# CPU.net
KiCad netlist of a schematic drawn in Altium Designer
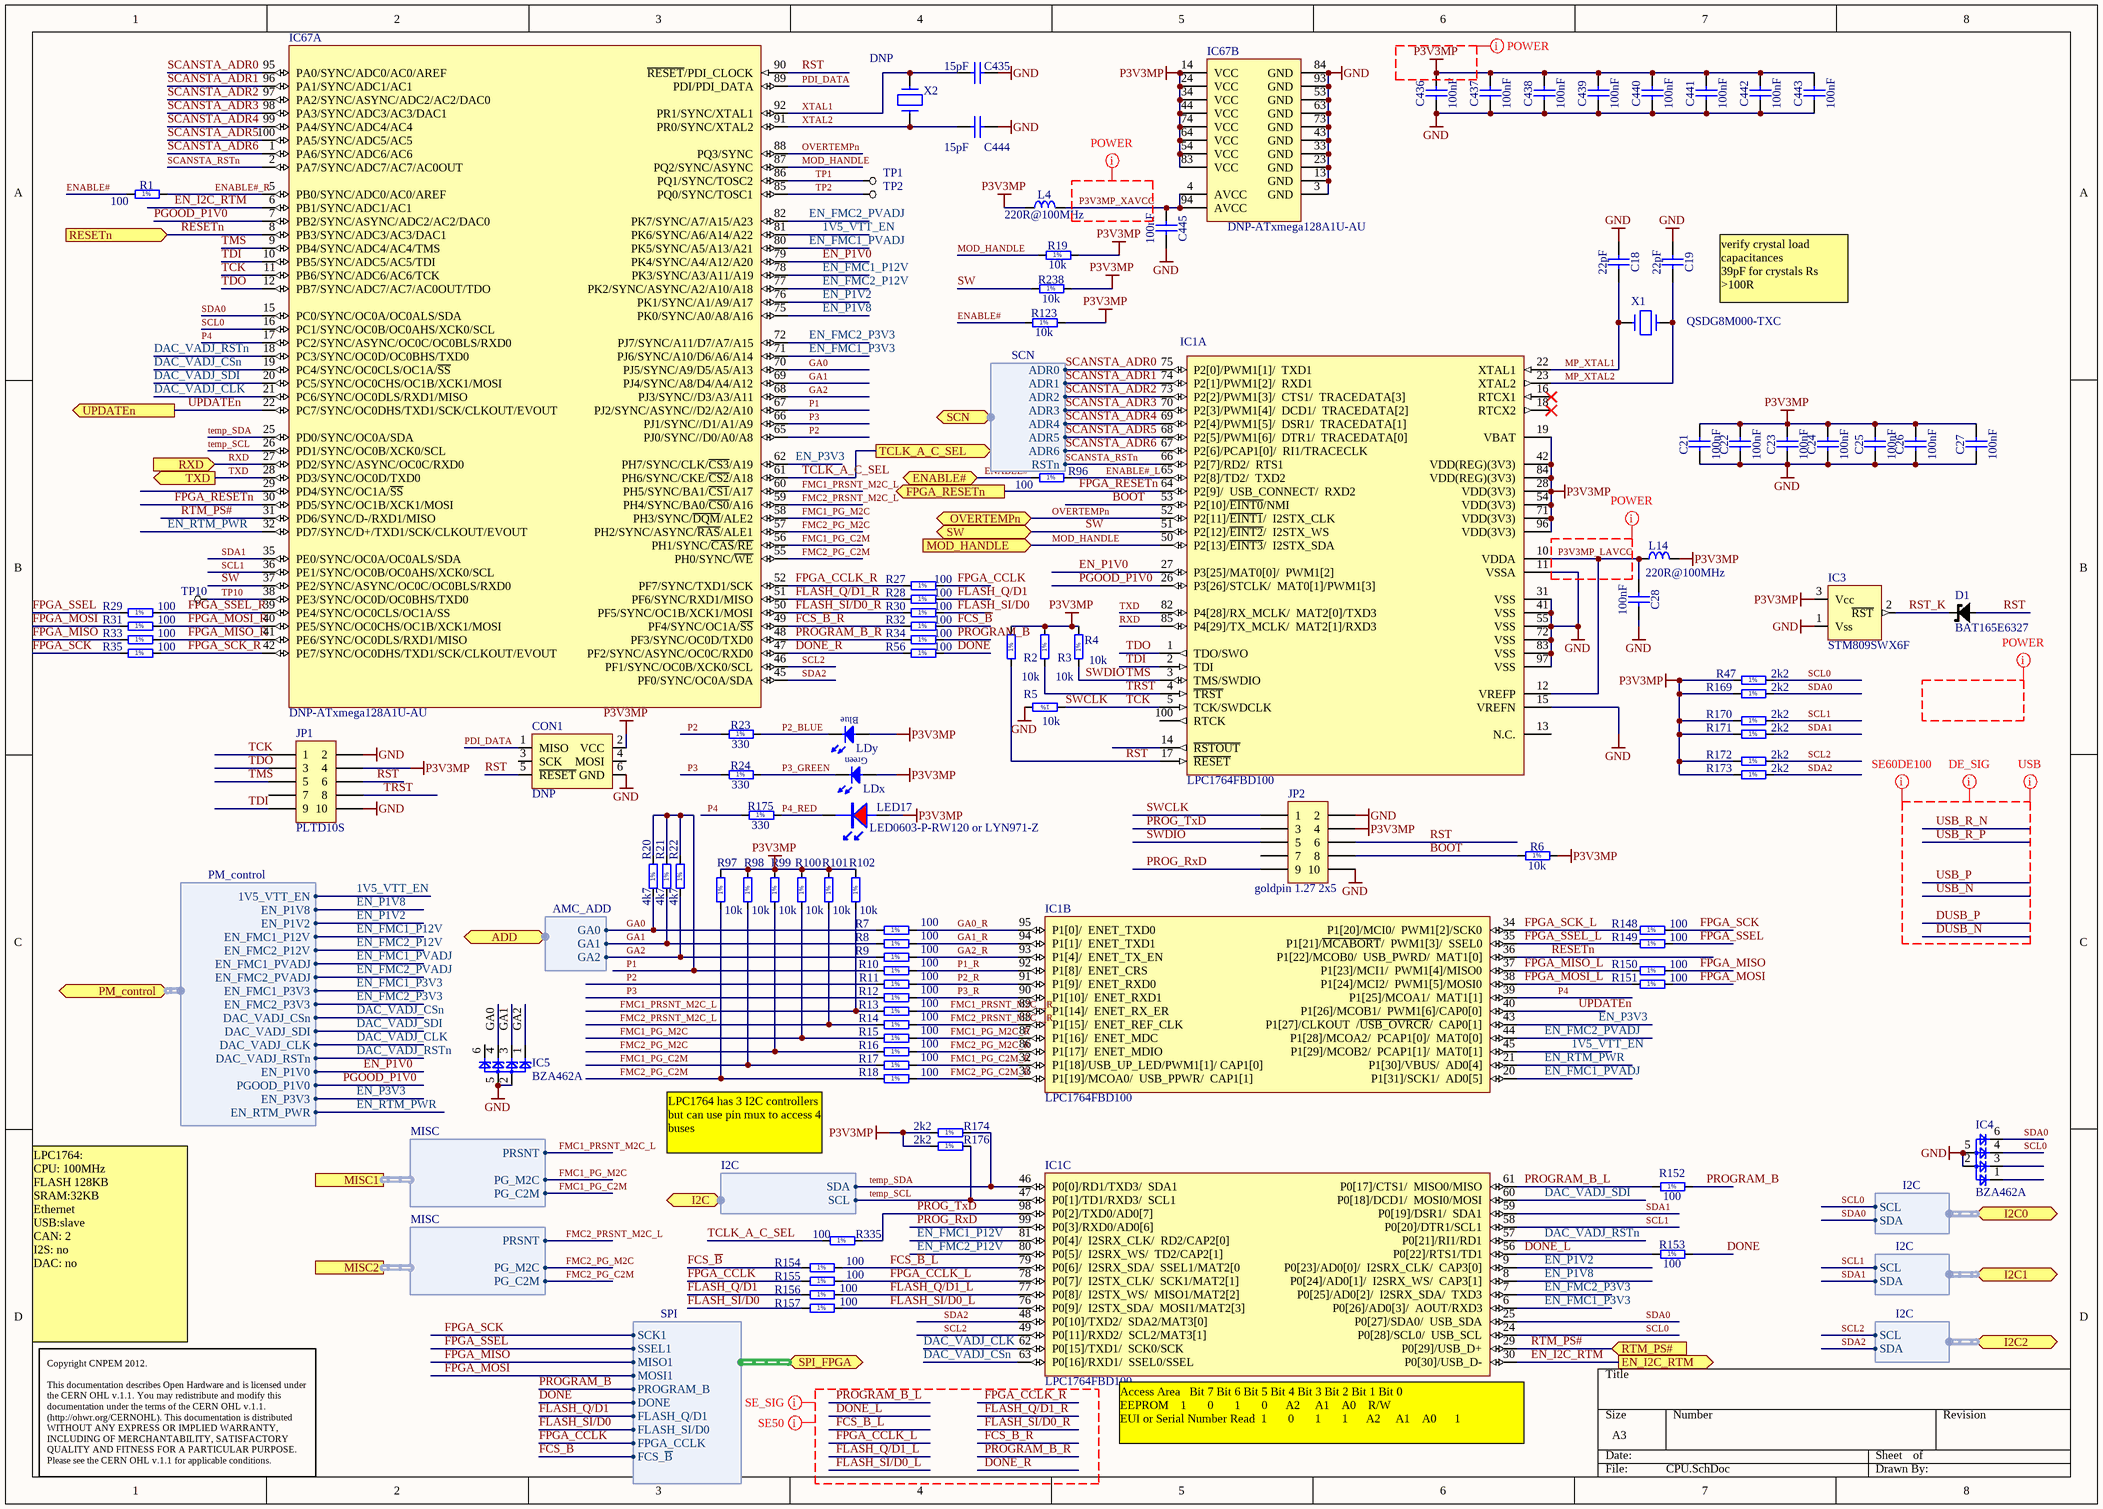
[diagram p0: CPU.SchDoc]

(export (version "E")
  (design (tool "Eeschema 10.0.6"))
  (components
    (comp (ref "C18")
      (value "22pF")
      (footprint "CAPC1005X55N")
      (description "Non-polarised capacitor")
      (fields
        (field (name "PART NUMBER") "CC0402_22PF_50V_5%_NP0")
        (field (name "VOLTAGE") "50V")
        (field (name "AUTHOR") "CERN DEM JLC")
      )
      (libsource (lib "Capacitors") (part "Capacitor - non polarized"))
    )
    (comp (ref "C19")
      (value "22pF")
      (footprint "CAPC1005X55N")
      (description "Non-polarised capacitor")
      (fields
        (field (name "PART NUMBER") "CC0402_22PF_50V_5%_NP0")
        (field (name "VOLTAGE") "50V")
        (field (name "AUTHOR") "CERN DEM JLC")
      )
      (libsource (lib "Capacitors") (part "Capacitor - non polarized"))
    )
    (comp (ref "C21")
      (value "100nF")
      (footprint "CAPC0603X33N")
      (description "Non-polarised capacitor")
      (fields
        (field (name "PART NUMBER") "CC0201_100NF_6.3V_10%_X5R")
        (field (name "VOLTAGE") "6.3V")
        (field (name "AUTHOR") "CERN DEM JLC")
      )
      (libsource (lib "Capacitors") (part "Capacitor - non polarized"))
    )
    (comp (ref "C22")
      (value "100nF")
      (footprint "CAPC0603X33N")
      (description "Non-polarised capacitor")
      (fields
        (field (name "PART NUMBER") "CC0201_100NF_6.3V_10%_X5R")
        (field (name "VOLTAGE") "6.3V")
        (field (name "AUTHOR") "CERN DEM JLC")
      )
      (libsource (lib "Capacitors") (part "Capacitor - non polarized"))
    )
    (comp (ref "C23")
      (value "100nF")
      (footprint "CAPC0603X33N")
      (description "Non-polarised capacitor")
      (fields
        (field (name "PART NUMBER") "CC0201_100NF_6.3V_10%_X5R")
        (field (name "VOLTAGE") "6.3V")
        (field (name "AUTHOR") "CERN DEM JLC")
      )
      (libsource (lib "Capacitors") (part "Capacitor - non polarized"))
    )
    (comp (ref "C24")
      (value "100nF")
      (footprint "CAPC0603X33N")
      (description "Non-polarised capacitor")
      (fields
        (field (name "PART NUMBER") "CC0201_100NF_6.3V_10%_X5R")
        (field (name "VOLTAGE") "6.3V")
        (field (name "AUTHOR") "CERN DEM JLC")
      )
      (libsource (lib "Capacitors") (part "Capacitor - non polarized"))
    )
    (comp (ref "C25")
      (value "100nF")
      (footprint "CAPC0603X33N")
      (description "Non-polarised capacitor")
      (fields
        (field (name "PART NUMBER") "CC0201_100NF_6.3V_10%_X5R")
        (field (name "VOLTAGE") "6.3V")
        (field (name "AUTHOR") "CERN DEM JLC")
      )
      (libsource (lib "Capacitors") (part "Capacitor - non polarized"))
    )
    (comp (ref "C26")
      (value "100nF")
      (footprint "CAPC0603X33N")
      (description "Non-polarised capacitor")
      (fields
        (field (name "PART NUMBER") "CC0201_100NF_6.3V_10%_X5R")
        (field (name "VOLTAGE") "6.3V")
        (field (name "AUTHOR") "CERN DEM JLC")
      )
      (libsource (lib "Capacitors") (part "Capacitor - non polarized"))
    )
    (comp (ref "C27")
      (value "100nF")
      (footprint "CAPC0603X33N")
      (description "Non-polarised capacitor")
      (fields
        (field (name "PART NUMBER") "CC0201_100NF_6.3V_10%_X5R")
        (field (name "VOLTAGE") "6.3V")
        (field (name "AUTHOR") "CERN DEM JLC")
      )
      (libsource (lib "Capacitors") (part "Capacitor - non polarized"))
    )
    (comp (ref "C28")
      (value "100nF")
      (footprint "CAPC0603X33N")
      (description "Non-polarised capacitor")
      (fields
        (field (name "PART NUMBER") "CC0201_100NF_6.3V_10%_X5R")
        (field (name "VOLTAGE") "6.3V")
        (field (name "AUTHOR") "CERN DEM JLC")
      )
      (libsource (lib "Capacitors") (part "Capacitor - non polarized"))
    )
    (comp (ref "C435")
      (value "15pF")
      (footprint "CAPC1005X55N")
      (description "Non-polarised capacitor")
      (fields
        (field (name "PART NUMBER") "CC0402_15PF_50V_5%_NP0")
        (field (name "VOLTAGE") "50V")
        (field (name "AUTHOR") "CERN DEM JLC")
      )
      (libsource (lib "Capacitors") (part "Capacitor - non polarized"))
    )
    (comp (ref "C436")
      (value "100nF")
      (footprint "CAPC0603X33N")
      (description "Non-polarised capacitor")
      (fields
        (field (name "PART NUMBER") "CC0201_100NF_6.3V_10%_X5R")
        (field (name "VOLTAGE") "6.3V")
        (field (name "AUTHOR") "CERN DEM JLC")
      )
      (libsource (lib "Capacitors") (part "Capacitor - non polarized"))
    )
    (comp (ref "C437")
      (value "100nF")
      (footprint "CAPC0603X33N")
      (description "Non-polarised capacitor")
      (fields
        (field (name "PART NUMBER") "CC0201_100NF_6.3V_10%_X5R")
        (field (name "VOLTAGE") "6.3V")
        (field (name "AUTHOR") "CERN DEM JLC")
      )
      (libsource (lib "Capacitors") (part "Capacitor - non polarized"))
    )
    (comp (ref "C438")
      (value "100nF")
      (footprint "CAPC0603X33N")
      (description "Non-polarised capacitor")
      (fields
        (field (name "PART NUMBER") "CC0201_100NF_6.3V_10%_X5R")
        (field (name "VOLTAGE") "6.3V")
        (field (name "AUTHOR") "CERN DEM JLC")
      )
      (libsource (lib "Capacitors") (part "Capacitor - non polarized"))
    )
    (comp (ref "C439")
      (value "100nF")
      (footprint "CAPC0603X33N")
      (description "Non-polarised capacitor")
      (fields
        (field (name "PART NUMBER") "CC0201_100NF_6.3V_10%_X5R")
        (field (name "VOLTAGE") "6.3V")
        (field (name "AUTHOR") "CERN DEM JLC")
      )
      (libsource (lib "Capacitors") (part "Capacitor - non polarized"))
    )
    (comp (ref "C440")
      (value "100nF")
      (footprint "CAPC0603X33N")
      (description "Non-polarised capacitor")
      (fields
        (field (name "PART NUMBER") "CC0201_100NF_6.3V_10%_X5R")
        (field (name "VOLTAGE") "6.3V")
        (field (name "AUTHOR") "CERN DEM JLC")
      )
      (libsource (lib "Capacitors") (part "Capacitor - non polarized"))
    )
    (comp (ref "C441")
      (value "100nF")
      (footprint "CAPC0603X33N")
      (description "Non-polarised capacitor")
      (fields
        (field (name "PART NUMBER") "CC0201_100NF_6.3V_10%_X5R")
        (field (name "VOLTAGE") "6.3V")
        (field (name "AUTHOR") "CERN DEM JLC")
      )
      (libsource (lib "Capacitors") (part "Capacitor - non polarized"))
    )
    (comp (ref "C442")
      (value "100nF")
      (footprint "CAPC0603X33N")
      (description "Non-polarised capacitor")
      (fields
        (field (name "PART NUMBER") "CC0201_100NF_6.3V_10%_X5R")
        (field (name "VOLTAGE") "6.3V")
        (field (name "AUTHOR") "CERN DEM JLC")
      )
      (libsource (lib "Capacitors") (part "Capacitor - non polarized"))
    )
    (comp (ref "C443")
      (value "100nF")
      (footprint "CAPC0603X33N")
      (description "Non-polarised capacitor")
      (fields
        (field (name "PART NUMBER") "CC0201_100NF_6.3V_10%_X5R")
        (field (name "VOLTAGE") "6.3V")
        (field (name "AUTHOR") "CERN DEM JLC")
      )
      (libsource (lib "Capacitors") (part "Capacitor - non polarized"))
    )
    (comp (ref "C444")
      (value "15pF")
      (footprint "CAPC1005X55N")
      (description "Non-polarised capacitor")
      (fields
        (field (name "PART NUMBER") "CC0402_15PF_50V_5%_NP0")
        (field (name "VOLTAGE") "50V")
        (field (name "AUTHOR") "CERN DEM JLC")
      )
      (libsource (lib "Capacitors") (part "Capacitor - non polarized"))
    )
    (comp (ref "C445")
      (value "100nF")
      (footprint "CAPC0603X33N")
      (description "Non-polarised capacitor")
      (fields
        (field (name "PART NUMBER") "CC0201_100NF_6.3V_10%_X5R")
        (field (name "VOLTAGE") "6.3V")
        (field (name "AUTHOR") "CERN DEM JLC")
      )
      (libsource (lib "Capacitors") (part "Capacitor - non polarized"))
    )
    (comp (ref "CON1")
      (value "DNP")
      (footprint "PLTD6S")
      (description "6x 2.54mm SMT  dual row pin header")
      (libsource (lib "LIBRARY_SCH") (part "CON_ISP"))
    )
    (comp (ref "D1")
      (value "BAT165E6327")
      (footprint "SOD323")
      (description "500mA, 40V, Shottky Diode")
      (libsource (lib "LIBRARY_SCH") (part "D_BAT165"))
    )
    (comp (ref "IC1")
      (value "LPC1764FBD100")
      (footprint "LQFP100-LPC")
      (description "ARM Cortex-M3 procesor")
      (libsource (lib "LIBRARY_SCH") (part "UPC_LPC1764"))
    )
    (comp (ref "IC3")
      (value "STM809SWX6F")
      (footprint "SOT-23")
      (description "2.93V  Reset circuit")
      (libsource (lib "LIBRARY_SCH") (part "VMON_STM809"))
    )
    (comp (ref "IC4")
      (value "BZA462A")
      (footprint "SOT23-6")
      (description "Quadruple 4V ESD transient voltage suppressor")
      (libsource (lib "LIBRARY_SCH") (part "D_TVS_BZA462A"))
    )
    (comp (ref "IC5")
      (value "BZA462A")
      (footprint "SOT23-6")
      (description "Quadruple 4V ESD transient voltage suppressor")
      (libsource (lib "LIBRARY_SCH") (part "D_TVS_BZA462A"))
    )
    (comp (ref "IC67")
      (value "DNP-ATxmega128A1U-AU")
      (footprint "TQFP100")
      (fields (field (name "PUBLISHER") "Altium Limited"))
      (libsource (lib "LIBRARY_SCH") (part "UPC_ATxmega128A1-AU"))
    )
    (comp (ref "JP1")
      (value "PLTD10S")
      (footprint "PLTD10S")
      (description "Goldpin 2.54mm, male header")
      (libsource (lib "LIBRARY_SCH") (part "CON_2x5 2.54 male SMT"))
    )
    (comp (ref "JP2")
      (value "goldpin 1.27 2x5")
      (footprint "CON_2x5_MINI")
      (description "PBTD10S")
      (libsource (lib "sch") (part "CON_HEADER 5X2"))
    )
    (comp (ref "L4")
      (value "220R@100MHz")
      (footprint "INDC2012X105N")
      (description "Inductor")
      (fields
        (field (name "PART NUMBER") "IND0805_MURATA_BLM21PG221SN1D")
        (field (name "POWER") "2A")
        (field (name "AUTHOR") "CERN DEM JLC")
      )
      (libsource (lib "Inductors & Transformers") (part "Inductor"))
    )
    (comp (ref "L14")
      (value "220R@100MHz")
      (footprint "INDC2012X105N")
      (description "Inductor")
      (fields
        (field (name "PART NUMBER") "IND0805_MURATA_BLM21PG221SN1D")
        (field (name "POWER") "2A")
        (field (name "AUTHOR") "CERN DEM JLC")
      )
      (libsource (lib "Inductors & Transformers") (part "Inductor"))
    )
    (comp (ref "LDx")
      (value "Green")
      (footprint "LED_AVAGO_HSME-C120")
      (description "LED Green Avago C120")
      (fields
        (field (name "PART NUMBER") "LED_AVAGO_HSME-C120")
        (field (name "MANUFACTURER") "AVAGO TECHNOLOGIES")
        (field (name "AUTHOR") "CERN DEM JMW")
      )
      (libsource (lib "LIBRARY_SCH") (part "LED_SMD_90deg_mini_G"))
    )
    (comp (ref "LDy")
      (value "Blue")
      (footprint "LED_AVAGO_HSME-C120")
      (description "LED Blue Avago C120")
      (fields
        (field (name "PART NUMBER") "LED_AVAGO_HSMR-C120")
        (field (name "MANUFACTURER") "AVAGO TECHNOLOGIES")
        (field (name "AUTHOR") "CERN DEM JMW")
      )
      (libsource (lib "LIBRARY_SCH") (part "LED_SMD_90deg_mini_B"))
    )
    (comp (ref "LED17")
      (value "LED0603-P-RW120 or LYN971-Z")
      (footprint "led_0603R")
      (description "LED 0603 red")
      (libsource (lib "LIBRARY_SCH") (part "LED_0603R"))
    )
    (comp (ref "R1")
      (value "100")
      (footprint "RESC1005X40N")
      (description "Resistor - 1%")
      (fields
        (field (name "PART NUMBER") "R0402_100R_1%_0.0625W_100PPM")
        (field (name "POWER") "0.0625W")
        (field (name "AUTHOR") "CERN DEM JLC")
      )
      (libsource (lib "Resistors") (part "Resistor - 1%"))
    )
    (comp (ref "R2")
      (value "10k")
      (footprint "RESC1005X40N")
      (description "Resistor - 1%")
      (fields
        (field (name "PART NUMBER") "R0402_10K_1%_0.0625W_100PPM")
        (field (name "POWER") "0.0625W")
        (field (name "AUTHOR") "CERN DEM JLC")
      )
      (libsource (lib "Resistors") (part "Resistor - 1%"))
    )
    (comp (ref "R3")
      (value "10k")
      (footprint "RESC1005X40N")
      (description "Resistor - 1%")
      (fields
        (field (name "PART NUMBER") "R0402_10K_1%_0.0625W_100PPM")
        (field (name "POWER") "0.0625W")
        (field (name "AUTHOR") "CERN DEM JLC")
      )
      (libsource (lib "Resistors") (part "Resistor - 1%"))
    )
    (comp (ref "R4")
      (value "10k")
      (footprint "RESC1005X40N")
      (description "Resistor - 1%")
      (fields
        (field (name "PART NUMBER") "R0402_10K_1%_0.0625W_100PPM")
        (field (name "POWER") "0.0625W")
        (field (name "AUTHOR") "CERN DEM JLC")
      )
      (libsource (lib "Resistors") (part "Resistor - 1%"))
    )
    (comp (ref "R5")
      (value "10k")
      (footprint "RESC1005X40N")
      (description "Resistor - 1%")
      (fields
        (field (name "PART NUMBER") "R0402_10K_1%_0.0625W_100PPM")
        (field (name "POWER") "0.0625W")
        (field (name "AUTHOR") "CERN DEM JLC")
      )
      (libsource (lib "Resistors") (part "Resistor - 1%"))
    )
    (comp (ref "R6")
      (value "10k")
      (footprint "RESC1005X40N")
      (description "Resistor - 1%")
      (fields
        (field (name "PART NUMBER") "R0402_10K_1%_0.0625W_100PPM")
        (field (name "POWER") "0.0625W")
        (field (name "AUTHOR") "CERN DEM JLC")
      )
      (libsource (lib "Resistors") (part "Resistor - 1%"))
    )
    (comp (ref "R7")
      (value "100")
      (footprint "RESC1005X40N")
      (description "Resistor - 1%")
      (fields
        (field (name "PART NUMBER") "R0402_100R_1%_0.0625W_100PPM")
        (field (name "POWER") "0.0625W")
        (field (name "AUTHOR") "CERN DEM JLC")
      )
      (libsource (lib "Resistors") (part "Resistor - 1%"))
    )
    (comp (ref "R8")
      (value "100")
      (footprint "RESC1005X40N")
      (description "Resistor - 1%")
      (fields
        (field (name "PART NUMBER") "R0402_100R_1%_0.0625W_100PPM")
        (field (name "POWER") "0.0625W")
        (field (name "AUTHOR") "CERN DEM JLC")
      )
      (libsource (lib "Resistors") (part "Resistor - 1%"))
    )
    (comp (ref "R9")
      (value "100")
      (footprint "RESC1005X40N")
      (description "Resistor - 1%")
      (fields
        (field (name "PART NUMBER") "R0402_100R_1%_0.0625W_100PPM")
        (field (name "POWER") "0.0625W")
        (field (name "AUTHOR") "CERN DEM JLC")
      )
      (libsource (lib "Resistors") (part "Resistor - 1%"))
    )
    (comp (ref "R10")
      (value "100")
      (footprint "RESC1005X40N")
      (description "Resistor - 1%")
      (fields
        (field (name "PART NUMBER") "R0402_100R_1%_0.0625W_100PPM")
        (field (name "POWER") "0.0625W")
        (field (name "AUTHOR") "CERN DEM JLC")
      )
      (libsource (lib "Resistors") (part "Resistor - 1%"))
    )
    (comp (ref "R11")
      (value "100")
      (footprint "RESC1005X40N")
      (description "Resistor - 1%")
      (fields
        (field (name "PART NUMBER") "R0402_100R_1%_0.0625W_100PPM")
        (field (name "POWER") "0.0625W")
        (field (name "AUTHOR") "CERN DEM JLC")
      )
      (libsource (lib "Resistors") (part "Resistor - 1%"))
    )
    (comp (ref "R12")
      (value "100")
      (footprint "RESC1005X40N")
      (description "Resistor - 1%")
      (fields
        (field (name "PART NUMBER") "R0402_100R_1%_0.0625W_100PPM")
        (field (name "POWER") "0.0625W")
        (field (name "AUTHOR") "CERN DEM JLC")
      )
      (libsource (lib "Resistors") (part "Resistor - 1%"))
    )
    (comp (ref "R13")
      (value "100")
      (footprint "RESC1005X40N")
      (description "Resistor - 1%")
      (fields
        (field (name "PART NUMBER") "R0402_100R_1%_0.0625W_100PPM")
        (field (name "POWER") "0.0625W")
        (field (name "AUTHOR") "CERN DEM JLC")
      )
      (libsource (lib "Resistors") (part "Resistor - 1%"))
    )
    (comp (ref "R14")
      (value "100")
      (footprint "RESC1005X40N")
      (description "Resistor - 1%")
      (fields
        (field (name "PART NUMBER") "R0402_100R_1%_0.0625W_100PPM")
        (field (name "POWER") "0.0625W")
        (field (name "AUTHOR") "CERN DEM JLC")
      )
      (libsource (lib "Resistors") (part "Resistor - 1%"))
    )
    (comp (ref "R15")
      (value "100")
      (footprint "RESC1005X40N")
      (description "Resistor - 1%")
      (fields
        (field (name "PART NUMBER") "R0402_100R_1%_0.0625W_100PPM")
        (field (name "POWER") "0.0625W")
        (field (name "AUTHOR") "CERN DEM JLC")
      )
      (libsource (lib "Resistors") (part "Resistor - 1%"))
    )
    (comp (ref "R16")
      (value "100")
      (footprint "RESC1005X40N")
      (description "Resistor - 1%")
      (fields
        (field (name "PART NUMBER") "R0402_100R_1%_0.0625W_100PPM")
        (field (name "POWER") "0.0625W")
        (field (name "AUTHOR") "CERN DEM JLC")
      )
      (libsource (lib "Resistors") (part "Resistor - 1%"))
    )
    (comp (ref "R17")
      (value "100")
      (footprint "RESC1005X40N")
      (description "Resistor - 1%")
      (fields
        (field (name "PART NUMBER") "R0402_100R_1%_0.0625W_100PPM")
        (field (name "POWER") "0.0625W")
        (field (name "AUTHOR") "CERN DEM JLC")
      )
      (libsource (lib "Resistors") (part "Resistor - 1%"))
    )
    (comp (ref "R18")
      (value "100")
      (footprint "RESC1005X40N")
      (description "Resistor - 1%")
      (fields
        (field (name "PART NUMBER") "R0402_100R_1%_0.0625W_100PPM")
        (field (name "POWER") "0.0625W")
        (field (name "AUTHOR") "CERN DEM JLC")
      )
      (libsource (lib "Resistors") (part "Resistor - 1%"))
    )
    (comp (ref "R19")
      (value "10k")
      (footprint "RESC1005X40N")
      (description "Resistor - 1%")
      (fields
        (field (name "PART NUMBER") "R0402_10K_1%_0.0625W_100PPM")
        (field (name "POWER") "0.0625W")
        (field (name "AUTHOR") "CERN DEM JLC")
      )
      (libsource (lib "Resistors") (part "Resistor - 1%"))
    )
    (comp (ref "R20")
      (value "4k7")
      (footprint "RESC1005X40N")
      (description "Resistor - 1%")
      (fields
        (field (name "PART NUMBER") "R0402_4K7_1%_0.0625W_100PPM")
        (field (name "POWER") "0.0625W")
        (field (name "AUTHOR") "CERN DEM JLC")
      )
      (libsource (lib "Resistors") (part "Resistor - 1%"))
    )
    (comp (ref "R21")
      (value "4k7")
      (footprint "RESC1005X40N")
      (description "Resistor - 1%")
      (fields
        (field (name "PART NUMBER") "R0402_4K7_1%_0.0625W_100PPM")
        (field (name "POWER") "0.0625W")
        (field (name "AUTHOR") "CERN DEM JLC")
      )
      (libsource (lib "Resistors") (part "Resistor - 1%"))
    )
    (comp (ref "R22")
      (value "4k7")
      (footprint "RESC1005X40N")
      (description "Resistor - 1%")
      (fields
        (field (name "PART NUMBER") "R0402_4K7_1%_0.0625W_100PPM")
        (field (name "POWER") "0.0625W")
        (field (name "AUTHOR") "CERN DEM JLC")
      )
      (libsource (lib "Resistors") (part "Resistor - 1%"))
    )
    (comp (ref "R23")
      (value "330")
      (footprint "RESC1005X40N")
      (description "Resistor - 1%")
      (fields
        (field (name "PART NUMBER") "R0402_330R_1%_0.0625W_100PPM")
        (field (name "POWER") "0.0625W")
        (field (name "AUTHOR") "CERN DEM JLC")
      )
      (libsource (lib "Resistors") (part "Resistor - 1%"))
    )
    (comp (ref "R24")
      (value "330")
      (footprint "RESC1005X40N")
      (description "Resistor - 1%")
      (fields
        (field (name "PART NUMBER") "R0402_330R_1%_0.0625W_100PPM")
        (field (name "POWER") "0.0625W")
        (field (name "AUTHOR") "CERN DEM JLC")
      )
      (libsource (lib "Resistors") (part "Resistor - 1%"))
    )
    (comp (ref "R27")
      (value "100")
      (footprint "RESC1005X40N")
      (description "Resistor - 1%")
      (fields
        (field (name "PART NUMBER") "R0402_100R_1%_0.0625W_100PPM")
        (field (name "POWER") "0.0625W")
        (field (name "AUTHOR") "CERN DEM JLC")
      )
      (libsource (lib "Resistors") (part "Resistor - 1%"))
    )
    (comp (ref "R28")
      (value "100")
      (footprint "RESC1005X40N")
      (description "Resistor - 1%")
      (fields
        (field (name "PART NUMBER") "R0402_100R_1%_0.0625W_100PPM")
        (field (name "POWER") "0.0625W")
        (field (name "AUTHOR") "CERN DEM JLC")
      )
      (libsource (lib "Resistors") (part "Resistor - 1%"))
    )
    (comp (ref "R29")
      (value "100")
      (footprint "RESC1005X40N")
      (description "Resistor - 1%")
      (fields
        (field (name "PART NUMBER") "R0402_100R_1%_0.0625W_100PPM")
        (field (name "POWER") "0.0625W")
        (field (name "AUTHOR") "CERN DEM JLC")
      )
      (libsource (lib "Resistors") (part "Resistor - 1%"))
    )
    (comp (ref "R30")
      (value "100")
      (footprint "RESC1005X40N")
      (description "Resistor - 1%")
      (fields
        (field (name "PART NUMBER") "R0402_100R_1%_0.0625W_100PPM")
        (field (name "POWER") "0.0625W")
        (field (name "AUTHOR") "CERN DEM JLC")
      )
      (libsource (lib "Resistors") (part "Resistor - 1%"))
    )
    (comp (ref "R31")
      (value "100")
      (footprint "RESC1005X40N")
      (description "Resistor - 1%")
      (fields
        (field (name "PART NUMBER") "R0402_100R_1%_0.0625W_100PPM")
        (field (name "POWER") "0.0625W")
        (field (name "AUTHOR") "CERN DEM JLC")
      )
      (libsource (lib "Resistors") (part "Resistor - 1%"))
    )
    (comp (ref "R32")
      (value "100")
      (footprint "RESC1005X40N")
      (description "Resistor - 1%")
      (fields
        (field (name "PART NUMBER") "R0402_100R_1%_0.0625W_100PPM")
        (field (name "POWER") "0.0625W")
        (field (name "AUTHOR") "CERN DEM JLC")
      )
      (libsource (lib "Resistors") (part "Resistor - 1%"))
    )
    (comp (ref "R33")
      (value "100")
      (footprint "RESC1005X40N")
      (description "Resistor - 1%")
      (fields
        (field (name "PART NUMBER") "R0402_100R_1%_0.0625W_100PPM")
        (field (name "POWER") "0.0625W")
        (field (name "AUTHOR") "CERN DEM JLC")
      )
      (libsource (lib "Resistors") (part "Resistor - 1%"))
    )
    (comp (ref "R34")
      (value "100")
      (footprint "RESC1005X40N")
      (description "Resistor - 1%")
      (fields
        (field (name "PART NUMBER") "R0402_100R_1%_0.0625W_100PPM")
        (field (name "POWER") "0.0625W")
        (field (name "AUTHOR") "CERN DEM JLC")
      )
      (libsource (lib "Resistors") (part "Resistor - 1%"))
    )
    (comp (ref "R35")
      (value "100")
      (footprint "RESC1005X40N")
      (description "Resistor - 1%")
      (fields
        (field (name "PART NUMBER") "R0402_100R_1%_0.0625W_100PPM")
        (field (name "POWER") "0.0625W")
        (field (name "AUTHOR") "CERN DEM JLC")
      )
      (libsource (lib "Resistors") (part "Resistor - 1%"))
    )
    (comp (ref "R47")
      (value "2k2")
      (footprint "RESC1005X40N")
      (description "Resistor - 1%")
      (fields
        (field (name "PART NUMBER") "R0402_2K2_1%_0.0625W_100PPM")
        (field (name "POWER") "0.0625W")
        (field (name "AUTHOR") "CERN DEM JLC")
      )
      (libsource (lib "Resistors") (part "Resistor - 1%"))
    )
    (comp (ref "R56")
      (value "100")
      (footprint "RESC1005X40N")
      (description "Resistor - 1%")
      (fields
        (field (name "PART NUMBER") "R0402_100R_1%_0.0625W_100PPM")
        (field (name "POWER") "0.0625W")
        (field (name "AUTHOR") "CERN DEM JLC")
      )
      (libsource (lib "Resistors") (part "Resistor - 1%"))
    )
    (comp (ref "R96")
      (value "100")
      (footprint "RESC1005X40N")
      (description "Resistor - 1%")
      (fields
        (field (name "PART NUMBER") "R0402_100R_1%_0.0625W_100PPM")
        (field (name "POWER") "0.0625W")
        (field (name "AUTHOR") "CERN DEM JLC")
      )
      (libsource (lib "Resistors") (part "Resistor - 1%"))
    )
    (comp (ref "R97")
      (value "10k")
      (footprint "RESC1005X40N")
      (description "Resistor - 1%")
      (fields
        (field (name "PART NUMBER") "R0402_10K_1%_0.0625W_100PPM")
        (field (name "POWER") "0.0625W")
        (field (name "AUTHOR") "CERN DEM JLC")
      )
      (libsource (lib "Resistors") (part "Resistor - 1%"))
    )
    (comp (ref "R98")
      (value "10k")
      (footprint "RESC1005X40N")
      (description "Resistor - 1%")
      (fields
        (field (name "PART NUMBER") "R0402_10K_1%_0.0625W_100PPM")
        (field (name "POWER") "0.0625W")
        (field (name "AUTHOR") "CERN DEM JLC")
      )
      (libsource (lib "Resistors") (part "Resistor - 1%"))
    )
    (comp (ref "R99")
      (value "10k")
      (footprint "RESC1005X40N")
      (description "Resistor - 1%")
      (fields
        (field (name "PART NUMBER") "R0402_10K_1%_0.0625W_100PPM")
        (field (name "POWER") "0.0625W")
        (field (name "AUTHOR") "CERN DEM JLC")
      )
      (libsource (lib "Resistors") (part "Resistor - 1%"))
    )
    (comp (ref "R100")
      (value "10k")
      (footprint "RESC1005X40N")
      (description "Resistor - 1%")
      (fields
        (field (name "PART NUMBER") "R0402_10K_1%_0.0625W_100PPM")
        (field (name "POWER") "0.0625W")
        (field (name "AUTHOR") "CERN DEM JLC")
      )
      (libsource (lib "Resistors") (part "Resistor - 1%"))
    )
    (comp (ref "R101")
      (value "10k")
      (footprint "RESC1005X40N")
      (description "Resistor - 1%")
      (fields
        (field (name "PART NUMBER") "R0402_10K_1%_0.0625W_100PPM")
        (field (name "POWER") "0.0625W")
        (field (name "AUTHOR") "CERN DEM JLC")
      )
      (libsource (lib "Resistors") (part "Resistor - 1%"))
    )
    (comp (ref "R102")
      (value "10k")
      (footprint "RESC1005X40N")
      (description "Resistor - 1%")
      (fields
        (field (name "PART NUMBER") "R0402_10K_1%_0.0625W_100PPM")
        (field (name "POWER") "0.0625W")
        (field (name "AUTHOR") "CERN DEM JLC")
      )
      (libsource (lib "Resistors") (part "Resistor - 1%"))
    )
    (comp (ref "R123")
      (value "10k")
      (footprint "RESC1005X40N")
      (description "Resistor - 1%")
      (fields
        (field (name "PART NUMBER") "R0402_10K_1%_0.0625W_100PPM")
        (field (name "POWER") "0.0625W")
        (field (name "AUTHOR") "CERN DEM JLC")
      )
      (libsource (lib "Resistors") (part "Resistor - 1%"))
    )
    (comp (ref "R148")
      (value "100")
      (footprint "RESC1005X40N")
      (description "Resistor - 1%")
      (fields
        (field (name "PART NUMBER") "R0402_100R_1%_0.0625W_100PPM")
        (field (name "POWER") "0.0625W")
        (field (name "AUTHOR") "CERN DEM JLC")
      )
      (libsource (lib "Resistors") (part "Resistor - 1%"))
    )
    (comp (ref "R149")
      (value "100")
      (footprint "RESC1005X40N")
      (description "Resistor - 1%")
      (fields
        (field (name "PART NUMBER") "R0402_100R_1%_0.0625W_100PPM")
        (field (name "POWER") "0.0625W")
        (field (name "AUTHOR") "CERN DEM JLC")
      )
      (libsource (lib "Resistors") (part "Resistor - 1%"))
    )
    (comp (ref "R150")
      (value "100")
      (footprint "RESC1005X40N")
      (description "Resistor - 1%")
      (fields
        (field (name "PART NUMBER") "R0402_100R_1%_0.0625W_100PPM")
        (field (name "POWER") "0.0625W")
        (field (name "AUTHOR") "CERN DEM JLC")
      )
      (libsource (lib "Resistors") (part "Resistor - 1%"))
    )
    (comp (ref "R151")
      (value "100")
      (footprint "RESC1005X40N")
      (description "Resistor - 1%")
      (fields
        (field (name "PART NUMBER") "R0402_100R_1%_0.0625W_100PPM")
        (field (name "POWER") "0.0625W")
        (field (name "AUTHOR") "CERN DEM JLC")
      )
      (libsource (lib "Resistors") (part "Resistor - 1%"))
    )
    (comp (ref "R152")
      (value "100")
      (footprint "RESC1005X40N")
      (description "Resistor - 1%")
      (fields
        (field (name "PART NUMBER") "R0402_100R_1%_0.0625W_100PPM")
        (field (name "POWER") "0.0625W")
        (field (name "AUTHOR") "CERN DEM JLC")
      )
      (libsource (lib "Resistors") (part "Resistor - 1%"))
    )
    (comp (ref "R153")
      (value "100")
      (footprint "RESC1005X40N")
      (description "Resistor - 1%")
      (fields
        (field (name "PART NUMBER") "R0402_100R_1%_0.0625W_100PPM")
        (field (name "POWER") "0.0625W")
        (field (name "AUTHOR") "CERN DEM JLC")
      )
      (libsource (lib "Resistors") (part "Resistor - 1%"))
    )
    (comp (ref "R154")
      (value "100")
      (footprint "RESC1005X40N")
      (description "Resistor - 1%")
      (fields
        (field (name "PART NUMBER") "R0402_100R_1%_0.0625W_100PPM")
        (field (name "POWER") "0.0625W")
        (field (name "AUTHOR") "CERN DEM JLC")
      )
      (libsource (lib "Resistors") (part "Resistor - 1%"))
    )
    (comp (ref "R155")
      (value "100")
      (footprint "RESC1005X40N")
      (description "Resistor - 1%")
      (fields
        (field (name "PART NUMBER") "R0402_100R_1%_0.0625W_100PPM")
        (field (name "POWER") "0.0625W")
        (field (name "AUTHOR") "CERN DEM JLC")
      )
      (libsource (lib "Resistors") (part "Resistor - 1%"))
    )
    (comp (ref "R156")
      (value "100")
      (footprint "RESC1005X40N")
      (description "Resistor - 1%")
      (fields
        (field (name "PART NUMBER") "R0402_100R_1%_0.0625W_100PPM")
        (field (name "POWER") "0.0625W")
        (field (name "AUTHOR") "CERN DEM JLC")
      )
      (libsource (lib "Resistors") (part "Resistor - 1%"))
    )
    (comp (ref "R157")
      (value "100")
      (footprint "RESC1005X40N")
      (description "Resistor - 1%")
      (fields
        (field (name "PART NUMBER") "R0402_100R_1%_0.0625W_100PPM")
        (field (name "POWER") "0.0625W")
        (field (name "AUTHOR") "CERN DEM JLC")
      )
      (libsource (lib "Resistors") (part "Resistor - 1%"))
    )
    (comp (ref "R169")
      (value "2k2")
      (footprint "RESC1005X40N")
      (description "Resistor - 1%")
      (fields
        (field (name "PART NUMBER") "R0402_2K2_1%_0.0625W_100PPM")
        (field (name "POWER") "0.0625W")
        (field (name "AUTHOR") "CERN DEM JLC")
      )
      (libsource (lib "Resistors") (part "Resistor - 1%"))
    )
    (comp (ref "R170")
      (value "2k2")
      (footprint "RESC1005X40N")
      (description "Resistor - 1%")
      (fields
        (field (name "PART NUMBER") "R0402_2K2_1%_0.0625W_100PPM")
        (field (name "POWER") "0.0625W")
        (field (name "AUTHOR") "CERN DEM JLC")
      )
      (libsource (lib "Resistors") (part "Resistor - 1%"))
    )
    (comp (ref "R171")
      (value "2k2")
      (footprint "RESC1005X40N")
      (description "Resistor - 1%")
      (fields
        (field (name "PART NUMBER") "R0402_2K2_1%_0.0625W_100PPM")
        (field (name "POWER") "0.0625W")
        (field (name "AUTHOR") "CERN DEM JLC")
      )
      (libsource (lib "Resistors") (part "Resistor - 1%"))
    )
    (comp (ref "R172")
      (value "2k2")
      (footprint "RESC1005X40N")
      (description "Resistor - 1%")
      (fields
        (field (name "PART NUMBER") "R0402_2K2_1%_0.0625W_100PPM")
        (field (name "POWER") "0.0625W")
        (field (name "AUTHOR") "CERN DEM JLC")
      )
      (libsource (lib "Resistors") (part "Resistor - 1%"))
    )
    (comp (ref "R173")
      (value "2k2")
      (footprint "RESC1005X40N")
      (description "Resistor - 1%")
      (fields
        (field (name "PART NUMBER") "R0402_2K2_1%_0.0625W_100PPM")
        (field (name "POWER") "0.0625W")
        (field (name "AUTHOR") "CERN DEM JLC")
      )
      (libsource (lib "Resistors") (part "Resistor - 1%"))
    )
    (comp (ref "R174")
      (value "2k2")
      (footprint "RESC1005X40N")
      (description "Resistor - 1%")
      (fields
        (field (name "PART NUMBER") "R0402_2K2_1%_0.0625W_100PPM")
        (field (name "POWER") "0.0625W")
        (field (name "AUTHOR") "CERN DEM JLC")
      )
      (libsource (lib "Resistors") (part "Resistor - 1%"))
    )
    (comp (ref "R175")
      (value "330")
      (footprint "RESC1005X40N")
      (description "Resistor - 1%")
      (fields
        (field (name "PART NUMBER") "R0402_330R_1%_0.0625W_100PPM")
        (field (name "POWER") "0.0625W")
        (field (name "AUTHOR") "CERN DEM JLC")
      )
      (libsource (lib "Resistors") (part "Resistor - 1%"))
    )
    (comp (ref "R176")
      (value "2k2")
      (footprint "RESC1005X40N")
      (description "Resistor - 1%")
      (fields
        (field (name "PART NUMBER") "R0402_2K2_1%_0.0625W_100PPM")
        (field (name "POWER") "0.0625W")
        (field (name "AUTHOR") "CERN DEM JLC")
      )
      (libsource (lib "Resistors") (part "Resistor - 1%"))
    )
    (comp (ref "R238")
      (value "10k")
      (footprint "RESC1005X40N")
      (description "Resistor - 1%")
      (fields
        (field (name "PART NUMBER") "R0402_10K_1%_0.0625W_100PPM")
        (field (name "POWER") "0.0625W")
        (field (name "AUTHOR") "CERN DEM JLC")
      )
      (libsource (lib "Resistors") (part "Resistor - 1%"))
    )
    (comp (ref "R335")
      (value "100")
      (footprint "RESC1005X40N")
      (description "Resistor - 1%")
      (fields
        (field (name "PART NUMBER") "R0402_100R_1%_0.0625W_100PPM")
        (field (name "POWER") "0.0625W")
        (field (name "AUTHOR") "CERN DEM JLC")
      )
      (libsource (lib "Resistors") (part "Resistor - 1%"))
    )
    (comp (ref "TP1")
      (value "TP")
      (footprint "TP")
      (description "Testpoint")
      (libsource (lib "LIBRARY_SCH") (part "TP"))
    )
    (comp (ref "TP2")
      (value "TP")
      (footprint "TP")
      (description "Testpoint")
      (libsource (lib "LIBRARY_SCH") (part "TP"))
    )
    (comp (ref "TP10")
      (value "TP")
      (footprint "TP")
      (description "Testpoint")
      (libsource (lib "LIBRARY_SCH") (part "TP"))
    )
    (comp (ref "X1")
      (value "QSDG8M000-TXC")
      (footprint "XTAL_5.0*3.2")
      (description "miniature crystal oscillator (Maritex) QSDG8M000-TXC")
      (libsource (lib "LIBRARY_SCH") (part "X_CRYSTAL_SMD_5.0*3.2"))
    )
    (comp (ref "X2")
      (value "DNP")
      (footprint "XTAL_5.0*3.2")
      (description "miniature crystal oscillator (Maritex) QSDG8M000-TXC")
      (libsource (lib "LIBRARY_SCH") (part "X_CRYSTAL_SMD_5.0*3.2"))
    )
  )
  (nets
    (net (code "7") (name "/1V5_VTT_EN") (class "Default")
      (node (ref "IC1") (pin "45") (pinfunction "P1[29]/MCOB2/__PCAP1[1]/__MAT0[1]_45") (pintype "bidirectional"))
      (node (ref "IC67") (pin "81") (pinfunction "PK6/SYNC/A6/A14/A22_81") (pintype "bidirectional"))
    )
    (net (code "8") (name "/BOOT") (class "Default")
      (node (ref "IC1") (pin "53") (pinfunction "P2[10]/~{EINT0}/NMI_53") (pintype "bidirectional"))
      (node (ref "JP2") (pin "8") (pinfunction "8_8") (pintype "passive"))
      (node (ref "R6") (pin "1") (pinfunction "1_1") (pintype "passive"))
    )
    (net (code "9") (name "/DAC_VADJ_CLK") (class "Default")
      (node (ref "IC1") (pin "62") (pinfunction "P0[15]/TXD1/__SCK0/SCK_62") (pintype "bidirectional"))
      (node (ref "IC67") (pin "21") (pinfunction "PC6/SYNC/OC0DLS/RXD1/MISO_21") (pintype "bidirectional"))
    )
    (net (code "10") (name "/DAC_VADJ_CSn") (class "Default")
      (node (ref "IC1") (pin "63") (pinfunction "P0[16]/RXD1/__SSEL0/SSEL_63") (pintype "bidirectional"))
      (node (ref "IC67") (pin "19") (pinfunction "PC4/SYNC/OC0CLS/OC1A/~{SS}_19") (pintype "bidirectional"))
    )
    (net (code "11") (name "/DAC_VADJ_RSTn") (class "Default")
      (node (ref "IC1") (pin "57") (pinfunction "P0[21]/RI1/RD1_57") (pintype "bidirectional"))
      (node (ref "IC67") (pin "18") (pinfunction "PC3/SYNC/OC0D/OC0BHS/TXD0_18") (pintype "bidirectional"))
    )
    (net (code "12") (name "/DAC_VADJ_SDI") (class "Default")
      (node (ref "IC1") (pin "60") (pinfunction "P0[18]/DCD1/__MOSI0/MOSI_60") (pintype "bidirectional"))
      (node (ref "IC67") (pin "20") (pinfunction "PC5/SYNC/OC0CHS/OC1B/XCK1/MOSI_20") (pintype "bidirectional"))
    )
    (net (code "13") (name "/DONE") (class "Default")
      (node (ref "R153") (pin "2") (pinfunction "2_2") (pintype "passive"))
      (node (ref "R56") (pin "2") (pinfunction "2_2") (pintype "passive"))
    )
    (net (code "14") (name "/DONE_L") (class "Default")
      (node (ref "IC1") (pin "56") (pinfunction "P0[22]/RTS1/TD1_56") (pintype "bidirectional"))
      (node (ref "R153") (pin "1") (pinfunction "1_1") (pintype "passive"))
    )
    (net (code "15") (name "/DONE_R") (class "Default")
      (node (ref "IC67") (pin "47") (pinfunction "PF2/SYNC/ASYNC/OC0C/RXD0_47") (pintype "bidirectional"))
      (node (ref "R56") (pin "1") (pinfunction "1_1") (pintype "passive"))
    )
    (net (code "18") (name "/ENABLE#") (class "Default")
      (node (ref "R1") (pin "1") (pinfunction "1_1") (pintype "passive"))
      (node (ref "R123") (pin "1") (pinfunction "1_1") (pintype "passive"))
      (node (ref "R96") (pin "1") (pinfunction "1_1") (pintype "passive"))
    )
    (net (code "19") (name "/ENABLE#_L") (class "Default")
      (node (ref "IC1") (pin "65") (pinfunction "P2[8]/TD2/__TXD2_65") (pintype "bidirectional"))
      (node (ref "R96") (pin "2") (pinfunction "2_2") (pintype "passive"))
    )
    (net (code "20") (name "/ENABLE#_R") (class "Default")
      (node (ref "IC67") (pin "5") (pinfunction "PB0/SYNC/ADC0/AC0/AREF_5") (pintype "bidirectional"))
      (node (ref "R1") (pin "2") (pinfunction "2_2") (pintype "passive"))
    )
    (net (code "21") (name "/EN_FMC1_P3V3") (class "Default")
      (node (ref "IC1") (pin "6") (pinfunction "P0[26]/AD0[3]/__AOUT/RXD3_6") (pintype "bidirectional"))
      (node (ref "IC67") (pin "71") (pinfunction "PJ6/SYNC/A10/D6/A6/A14_71") (pintype "bidirectional"))
    )
    (net (code "22") (name "/EN_FMC1_P12V") (class "Default")
      (node (ref "IC1") (pin "81") (pinfunction "P0[4]/__I2SRX_CLK/__RD2/CAP2[0]_81") (pintype "bidirectional"))
      (node (ref "IC67") (pin "78") (pinfunction "PK3/SYNC/A3/A11/A19_78") (pintype "bidirectional"))
    )
    (net (code "23") (name "/EN_FMC1_PVADJ") (class "Default")
      (node (ref "IC1") (pin "20") (pinfunction "P1[31]/SCK1/__AD0[5]_20") (pintype "bidirectional"))
      (node (ref "IC67") (pin "80") (pinfunction "PK5/SYNC/A5/A13/A21_80") (pintype "bidirectional"))
    )
    (net (code "24") (name "/EN_FMC2_P3V3") (class "Default")
      (node (ref "IC1") (pin "7") (pinfunction "P0[25]/AD0[2]/__I2SRX_SDA/__TXD3_7") (pintype "bidirectional"))
      (node (ref "IC67") (pin "72") (pinfunction "PJ7/SYNC/A11/D7/A7/A15_72") (pintype "bidirectional"))
    )
    (net (code "25") (name "/EN_FMC2_P12V") (class "Default")
      (node (ref "IC1") (pin "80") (pinfunction "P0[5]/__I2SRX_WS/__TD2/CAP2[1]_80") (pintype "bidirectional"))
      (node (ref "IC67") (pin "77") (pinfunction "PK2/SYNC/ASYNC/A2/A10/A18_77") (pintype "bidirectional"))
    )
    (net (code "26") (name "/EN_FMC2_PVADJ") (class "Default")
      (node (ref "IC1") (pin "44") (pinfunction "P1[28]/MCOA2/__PCAP1[0]/__MAT0[0]_44") (pintype "bidirectional"))
      (node (ref "IC67") (pin "82") (pinfunction "PK7/SYNC/A7/A15/A23_82") (pintype "bidirectional"))
    )
    (net (code "27") (name "/EN_I2C_RTM") (class "Default")
      (node (ref "IC1") (pin "30") (pinfunction "P0[30]/USB_D-_30") (pintype "bidirectional"))
      (node (ref "IC67") (pin "6") (pinfunction "PB1/SYNC/ADC1/AC1_6") (pintype "bidirectional"))
    )
    (net (code "28") (name "/EN_P1V0") (class "Default")
      (node (ref "IC1") (pin "27") (pinfunction "P3[25]/MAT0[0]/__PWM1[2]_27") (pintype "bidirectional"))
      (node (ref "IC67") (pin "79") (pinfunction "PK4/SYNC/A4/A12/A20_79") (pintype "bidirectional"))
    )
    (net (code "29") (name "/EN_P1V2") (class "Default")
      (node (ref "IC1") (pin "9") (pinfunction "P0[23]/AD0[0]/__I2SRX_CLK/__CAP3[0]_9") (pintype "bidirectional"))
      (node (ref "IC67") (pin "76") (pinfunction "PK1/SYNC/A1/A9/A17_76") (pintype "bidirectional"))
    )
    (net (code "30") (name "/EN_P1V8") (class "Default")
      (node (ref "IC1") (pin "8") (pinfunction "P0[24]/AD0[1]/__I2SRX_WS/__CAP3[1]_8") (pintype "bidirectional"))
      (node (ref "IC67") (pin "75") (pinfunction "PK0/SYNC/A0/A8/A16_75") (pintype "bidirectional"))
    )
    (net (code "31") (name "/EN_P3V3") (class "Default")
      (node (ref "IC1") (pin "43") (pinfunction "P1[27]/CLKOUT__/~{USB_OVRCR}/__CAP0[1]_43") (pintype "bidirectional"))
      (node (ref "IC67") (pin "62") (pinfunction "PH7/SYNC/CLK/~{CS3}/A19_62") (pintype "bidirectional"))
    )
    (net (code "32") (name "/EN_RTM_PWR") (class "Default")
      (node (ref "IC1") (pin "21") (pinfunction "P1[30]/VBUS/__AD0[4]_21") (pintype "bidirectional"))
      (node (ref "IC67") (pin "32") (pinfunction "PD7/SYNC/D+/TXD1/SCK/CLKOUT/EVOUT_32") (pintype "bidirectional"))
    )
    (net (code "33") (name "/FCS_~{B}") (class "Default")
      (node (ref "R154") (pin "1") (pinfunction "1_1") (pintype "passive"))
      (node (ref "R32") (pin "2") (pinfunction "2_2") (pintype "passive"))
    )
    (net (code "34") (name "/FCS_~{B}_L") (class "Default")
      (node (ref "IC1") (pin "79") (pinfunction "P0[6]/__I2SRX_SDA/__SSEL1/MAT2[0_79") (pintype "bidirectional"))
      (node (ref "R154") (pin "2") (pinfunction "2_2") (pintype "passive"))
    )
    (net (code "35") (name "/FCS_~{B}_R") (class "Default")
      (node (ref "IC67") (pin "49") (pinfunction "PF4/SYNC/OC1A/~{SS}_49") (pintype "bidirectional"))
      (node (ref "R32") (pin "1") (pinfunction "1_1") (pintype "passive"))
    )
    (net (code "36") (name "/FLASH_Q{slash}D1") (class "Default")
      (node (ref "R156") (pin "1") (pinfunction "1_1") (pintype "passive"))
      (node (ref "R28") (pin "2") (pinfunction "2_2") (pintype "passive"))
    )
    (net (code "37") (name "/FLASH_Q{slash}D1_L") (class "Default")
      (node (ref "IC1") (pin "77") (pinfunction "P0[8]/__I2STX_WS/__MISO1/MAT2[2]_77") (pintype "bidirectional"))
      (node (ref "R156") (pin "2") (pinfunction "2_2") (pintype "passive"))
    )
    (net (code "38") (name "/FLASH_Q{slash}D1_R") (class "Default")
      (node (ref "IC67") (pin "51") (pinfunction "PF6/SYNC/RXD1/MISO_51") (pintype "bidirectional"))
      (node (ref "R28") (pin "1") (pinfunction "1_1") (pintype "passive"))
    )
    (net (code "39") (name "/FLASH_SI{slash}D0") (class "Default")
      (node (ref "R157") (pin "1") (pinfunction "1_1") (pintype "passive"))
      (node (ref "R30") (pin "2") (pinfunction "2_2") (pintype "passive"))
    )
    (net (code "40") (name "/FLASH_SI{slash}D0_L") (class "Default")
      (node (ref "IC1") (pin "76") (pinfunction "P0[9]/__I2STX_SDA/__MOSI1/MAT2[3]_76") (pintype "bidirectional"))
      (node (ref "R157") (pin "2") (pinfunction "2_2") (pintype "passive"))
    )
    (net (code "41") (name "/FLASH_SI{slash}D0_R") (class "Default")
      (node (ref "IC67") (pin "50") (pinfunction "PF5/SYNC/OC1B/XCK1/MOSI_50") (pintype "bidirectional"))
      (node (ref "R30") (pin "1") (pinfunction "1_1") (pintype "passive"))
    )
    (net (code "42") (name "/FMC1_PG_C2M") (class "Default")
      (node (ref "IC67") (pin "56") (pinfunction "PH1/SYNC/~{CAS}/~{RE}_56") (pintype "bidirectional"))
      (node (ref "R17") (pin "1") (pinfunction "1_1") (pintype "passive"))
      (node (ref "R98") (pin "1") (pinfunction "1_1") (pintype "passive"))
    )
    (net (code "43") (name "/FMC1_PG_C2M_R") (class "Default")
      (node (ref "IC1") (pin "32") (pinfunction "P1[18]/USB_UP_LED/PWM1[1]/_CAP1[0]_32") (pintype "bidirectional"))
      (node (ref "R17") (pin "2") (pinfunction "2_2") (pintype "passive"))
    )
    (net (code "44") (name "/FMC1_PG_M2C") (class "Default")
      (node (ref "IC67") (pin "58") (pinfunction "PH3/SYNC/~{DQM}/ALE2_58") (pintype "bidirectional"))
      (node (ref "R100") (pin "1") (pinfunction "1_1") (pintype "passive"))
      (node (ref "R15") (pin "1") (pinfunction "1_1") (pintype "passive"))
    )
    (net (code "45") (name "/FMC1_PG_M2C_R") (class "Default")
      (node (ref "IC1") (pin "87") (pinfunction "P1[16]/__ENET_MDC_87") (pintype "bidirectional"))
      (node (ref "R15") (pin "2") (pinfunction "2_2") (pintype "passive"))
    )
    (net (code "46") (name "/FMC1_PRSNT_M2C_L") (class "Default")
      (node (ref "IC67") (pin "60") (pinfunction "PH5/SYNC/BA1/~{CS1}/A17_60") (pintype "bidirectional"))
      (node (ref "R102") (pin "1") (pinfunction "1_1") (pintype "passive"))
      (node (ref "R13") (pin "1") (pinfunction "1_1") (pintype "passive"))
    )
    (net (code "47") (name "/FMC1_PRSNT_M2C__R") (class "Default")
      (node (ref "IC1") (pin "89") (pinfunction "P1[14]/__ENET_RX_ER_89") (pintype "bidirectional"))
      (node (ref "R13") (pin "2") (pinfunction "2_2") (pintype "passive"))
    )
    (net (code "48") (name "/FMC2_PG_C2M") (class "Default")
      (node (ref "IC67") (pin "55") (pinfunction "PH0/SYNC/~{WE}_55") (pintype "bidirectional"))
      (node (ref "R18") (pin "1") (pinfunction "1_1") (pintype "passive"))
      (node (ref "R97") (pin "1") (pinfunction "1_1") (pintype "passive"))
    )
    (net (code "49") (name "/FMC2_PG_C2M_R") (class "Default")
      (node (ref "IC1") (pin "33") (pinfunction "P1[19]/MCOA0/__USB_PPWR/__CAP1[1]_33") (pintype "bidirectional"))
      (node (ref "R18") (pin "2") (pinfunction "2_2") (pintype "passive"))
    )
    (net (code "50") (name "/FMC2_PG_M2C") (class "Default")
      (node (ref "IC67") (pin "57") (pinfunction "PH2/SYNC/ASYNC/~{RAS}/ALE1_57") (pintype "bidirectional"))
      (node (ref "R16") (pin "1") (pinfunction "1_1") (pintype "passive"))
      (node (ref "R99") (pin "1") (pinfunction "1_1") (pintype "passive"))
    )
    (net (code "51") (name "/FMC2_PG_M2C_R") (class "Default")
      (node (ref "IC1") (pin "86") (pinfunction "P1[17]/__ENET_MDIO_86") (pintype "bidirectional"))
      (node (ref "R16") (pin "2") (pinfunction "2_2") (pintype "passive"))
    )
    (net (code "52") (name "/FMC2_PRSNT_M2C_L") (class "Default")
      (node (ref "IC67") (pin "59") (pinfunction "PH4/SYNC/BA0/~{CS0}/A16_59") (pintype "bidirectional"))
      (node (ref "R101") (pin "1") (pinfunction "1_1") (pintype "passive"))
      (node (ref "R14") (pin "1") (pinfunction "1_1") (pintype "passive"))
    )
    (net (code "53") (name "/FMC2_PRSNT_M2C__R") (class "Default")
      (node (ref "IC1") (pin "88") (pinfunction "P1[15]/__ENET_REF_CLK_88") (pintype "bidirectional"))
      (node (ref "R14") (pin "2") (pinfunction "2_2") (pintype "passive"))
    )
    (net (code "54") (name "/FPGA_CCLK") (class "Default")
      (node (ref "R155") (pin "1") (pinfunction "1_1") (pintype "passive"))
      (node (ref "R27") (pin "2") (pinfunction "2_2") (pintype "passive"))
    )
    (net (code "55") (name "/FPGA_CCLK_L") (class "Default")
      (node (ref "IC1") (pin "78") (pinfunction "P0[7]/__I2STX_CLK/__SCK1/MAT2[1]_78") (pintype "bidirectional"))
      (node (ref "R155") (pin "2") (pinfunction "2_2") (pintype "passive"))
    )
    (net (code "56") (name "/FPGA_CCLK_R") (class "Default")
      (node (ref "IC67") (pin "52") (pinfunction "PF7/SYNC/TXD1/SCK_52") (pintype "bidirectional"))
      (node (ref "R27") (pin "1") (pinfunction "1_1") (pintype "passive"))
    )
    (net (code "57") (name "/FPGA_MISO") (class "Default")
      (node (ref "R150") (pin "2") (pinfunction "2_2") (pintype "passive"))
      (node (ref "R33") (pin "1") (pinfunction "1_1") (pintype "passive"))
    )
    (net (code "58") (name "/FPGA_MISO_L") (class "Default")
      (node (ref "IC1") (pin "37") (pinfunction "P1[23]/MCI1/__PWM1[4]/MISO0_37") (pintype "bidirectional"))
      (node (ref "R150") (pin "1") (pinfunction "1_1") (pintype "passive"))
    )
    (net (code "59") (name "/FPGA_MISO_R") (class "Default")
      (node (ref "IC67") (pin "41") (pinfunction "PE6/SYNC/OC0DLS/RXD1/MISO_41") (pintype "bidirectional"))
      (node (ref "R33") (pin "2") (pinfunction "2_2") (pintype "passive"))
    )
    (net (code "60") (name "/FPGA_MOSI") (class "Default")
      (node (ref "R151") (pin "2") (pinfunction "2_2") (pintype "passive"))
      (node (ref "R31") (pin "1") (pinfunction "1_1") (pintype "passive"))
    )
    (net (code "61") (name "/FPGA_MOSI_L") (class "Default")
      (node (ref "IC1") (pin "38") (pinfunction "P1[24]/MCI2/__PWM1[5]/MOSI0_38") (pintype "bidirectional"))
      (node (ref "R151") (pin "1") (pinfunction "1_1") (pintype "passive"))
    )
    (net (code "62") (name "/FPGA_MOSI_R") (class "Default")
      (node (ref "IC67") (pin "40") (pinfunction "PE5/SYNC/OC0CHS/OC1B/XCK1/MOSI_40") (pintype "bidirectional"))
      (node (ref "R31") (pin "2") (pinfunction "2_2") (pintype "passive"))
    )
    (net (code "63") (name "/FPGA_RESETn") (class "Default")
      (node (ref "IC1") (pin "64") (pinfunction "P2[9]/__USB_CONNECT/__RXD2_64") (pintype "bidirectional"))
      (node (ref "IC67") (pin "30") (pinfunction "PD5/SYNC/OC1B/XCK1/MOSI_30") (pintype "bidirectional"))
    )
    (net (code "64") (name "/FPGA_SCK") (class "Default")
      (node (ref "R148") (pin "2") (pinfunction "2_2") (pintype "passive"))
      (node (ref "R35") (pin "1") (pinfunction "1_1") (pintype "passive"))
    )
    (net (code "65") (name "/FPGA_SCK_L") (class "Default")
      (node (ref "IC1") (pin "34") (pinfunction "P1[20]/MCI0/__PWM1[2]/SCK0_34") (pintype "bidirectional"))
      (node (ref "R148") (pin "1") (pinfunction "1_1") (pintype "passive"))
    )
    (net (code "66") (name "/FPGA_SCK_R") (class "Default")
      (node (ref "IC67") (pin "42") (pinfunction "PE7/SYNC/OC0DHS/TXD1/SCK/CLKOUT/EVOUT_42") (pintype "bidirectional"))
      (node (ref "R35") (pin "2") (pinfunction "2_2") (pintype "passive"))
    )
    (net (code "67") (name "/FPGA_SSEL") (class "Default")
      (node (ref "R149") (pin "2") (pinfunction "2_2") (pintype "passive"))
      (node (ref "R29") (pin "1") (pinfunction "1_1") (pintype "passive"))
    )
    (net (code "68") (name "/FPGA_SSEL_L") (class "Default")
      (node (ref "IC1") (pin "35") (pinfunction "P1[21]/~{MCABORT}/__PWM1[3]/__SSEL0_35") (pintype "bidirectional"))
      (node (ref "R149") (pin "1") (pinfunction "1_1") (pintype "passive"))
    )
    (net (code "69") (name "/FPGA_SSEL_R") (class "Default")
      (node (ref "IC67") (pin "39") (pinfunction "PE4/SYNC/OC0CLS/OC1A/SS_39") (pintype "bidirectional"))
      (node (ref "R29") (pin "2") (pinfunction "2_2") (pintype "passive"))
    )
    (net (code "70") (name "/GA0") (class "Default")
      (node (ref "IC5") (pin "4") (pinfunction "4_4") (pintype "passive"))
      (node (ref "IC67") (pin "70") (pinfunction "PJ5/SYNC/A9/D5/A5/A13_70") (pintype "bidirectional"))
      (node (ref "R20") (pin "1") (pinfunction "1_1") (pintype "passive"))
      (node (ref "R7") (pin "1") (pinfunction "1_1") (pintype "passive"))
    )
    (net (code "71") (name "/GA0_R") (class "Default")
      (node (ref "IC1") (pin "95") (pinfunction "P1[0]/__ENET_TXD0_95") (pintype "bidirectional"))
      (node (ref "R7") (pin "2") (pinfunction "2_2") (pintype "passive"))
    )
    (net (code "72") (name "/GA1") (class "Default")
      (node (ref "IC5") (pin "3") (pinfunction "3_3") (pintype "passive"))
      (node (ref "IC67") (pin "69") (pinfunction "PJ4/SYNC/A8/D4/A4/A12_69") (pintype "bidirectional"))
      (node (ref "R21") (pin "1") (pinfunction "1_1") (pintype "passive"))
      (node (ref "R8") (pin "1") (pinfunction "1_1") (pintype "passive"))
    )
    (net (code "73") (name "/GA1_R") (class "Default")
      (node (ref "IC1") (pin "94") (pinfunction "P1[1]/__ENET_TXD1_94") (pintype "bidirectional"))
      (node (ref "R8") (pin "2") (pinfunction "2_2") (pintype "passive"))
    )
    (net (code "74") (name "/GA2") (class "Default")
      (node (ref "IC5") (pin "1") (pinfunction "1_1") (pintype "passive"))
      (node (ref "IC67") (pin "68") (pinfunction "PJ3/SYNC//D3/A3/A11_68") (pintype "bidirectional"))
      (node (ref "R22") (pin "1") (pinfunction "1_1") (pintype "passive"))
      (node (ref "R9") (pin "1") (pinfunction "1_1") (pintype "passive"))
    )
    (net (code "75") (name "/GA2_R") (class "Default")
      (node (ref "IC1") (pin "93") (pinfunction "P1[4]/__ENET_TX_EN_93") (pintype "bidirectional"))
      (node (ref "R9") (pin "2") (pinfunction "2_2") (pintype "passive"))
    )
    (net (code "76") (name "/MOD_HANDLE") (class "Default")
      (node (ref "IC1") (pin "50") (pinfunction "P2[13]/~{EINT3}/__I2STX_SDA_50") (pintype "bidirectional"))
      (node (ref "IC67") (pin "87") (pinfunction "PQ2/SYNC/ASYNC_87") (pintype "bidirectional"))
      (node (ref "R19") (pin "1") (pinfunction "1_1") (pintype "passive"))
    )
    (net (code "77") (name "/MP_XTAL1") (class "Default")
      (node (ref "C18") (pin "2") (pinfunction "2_2") (pintype "passive"))
      (node (ref "IC1") (pin "22") (pinfunction "XTAL1_22") (pintype "input"))
      (node (ref "X1") (pin "1") (pinfunction "1_1") (pintype "passive"))
    )
    (net (code "78") (name "/MP_XTAL2") (class "Default")
      (node (ref "C19") (pin "2") (pinfunction "2_2") (pintype "passive"))
      (node (ref "IC1") (pin "23") (pinfunction "XTAL2_23") (pintype "output"))
      (node (ref "X1") (pin "2") (pinfunction "2_2") (pintype "passive"))
    )
    (net (code "79") (name "/OVERTEMPn") (class "Default")
      (node (ref "IC1") (pin "52") (pinfunction "P2[11]/~{EINT1}/__I2STX_CLK_52") (pintype "bidirectional"))
      (node (ref "IC67") (pin "88") (pinfunction "PQ3/SYNC_88") (pintype "bidirectional"))
    )
    (net (code "80") (name "/P1") (class "Default")
      (node (ref "IC67") (pin "67") (pinfunction "PJ2/SYNC/ASYNC//D2/A2/A10_67") (pintype "bidirectional"))
      (node (ref "R10") (pin "1") (pinfunction "1_1") (pintype "passive"))
      (node (ref "R20") (pin "2") (pinfunction "2_2") (pintype "passive"))
      (node (ref "R21") (pin "2") (pinfunction "2_2") (pintype "passive"))
      (node (ref "R22") (pin "2") (pinfunction "2_2") (pintype "passive"))
    )
    (net (code "81") (name "/P1_R") (class "Default")
      (node (ref "IC1") (pin "92") (pinfunction "P1[8]/__ENET_CRS_92") (pintype "bidirectional"))
      (node (ref "R10") (pin "2") (pinfunction "2_2") (pintype "passive"))
    )
    (net (code "82") (name "/P2") (class "Default")
      (node (ref "IC67") (pin "65") (pinfunction "PJ0/SYNC//D0/A0/A8_65") (pintype "bidirectional"))
      (node (ref "R11") (pin "1") (pinfunction "1_1") (pintype "passive"))
      (node (ref "R23") (pin "1") (pinfunction "1_1") (pintype "passive"))
    )
    (net (code "83") (name "/P2_BLUE") (class "Default")
      (node (ref "LDy") (pin "2") (pinfunction "C_2") (pintype "passive"))
      (node (ref "R23") (pin "2") (pinfunction "2_2") (pintype "passive"))
    )
    (net (code "84") (name "/P2_R") (class "Default")
      (node (ref "IC1") (pin "91") (pinfunction "P1[9]/__ENET_RXD0_91") (pintype "bidirectional"))
      (node (ref "R11") (pin "2") (pinfunction "2_2") (pintype "passive"))
    )
    (net (code "85") (name "/P3") (class "Default")
      (node (ref "IC67") (pin "66") (pinfunction "PJ1/SYNC//D1/A1/A9_66") (pintype "bidirectional"))
      (node (ref "R12") (pin "1") (pinfunction "1_1") (pintype "passive"))
      (node (ref "R24") (pin "1") (pinfunction "1_1") (pintype "passive"))
    )
    (net (code "86") (name "/P3V3MP_LAVCC") (class "Default")
      (node (ref "C28") (pin "1") (pinfunction "1_1") (pintype "passive"))
      (node (ref "IC1") (pin "10") (pinfunction "VDDA_10") (pintype "power_in"))
      (node (ref "IC1") (pin "12") (pinfunction "VREFP_12") (pintype "power_in"))
      (node (ref "L14") (pin "1") (pinfunction "1_1") (pintype "passive"))
    )
    (net (code "87") (name "/P3V3MP_XAVCC") (class "Default")
      (node (ref "C445") (pin "1") (pinfunction "1_1") (pintype "passive"))
      (node (ref "IC67") (pin "4") (pinfunction "AVCC_4") (pintype "power_in"))
      (node (ref "IC67") (pin "94") (pinfunction "AVCC_94") (pintype "power_in"))
      (node (ref "L4") (pin "2") (pinfunction "2_2") (pintype "passive"))
    )
    (net (code "88") (name "/P3_GREEN") (class "Default")
      (node (ref "LDx") (pin "2") (pinfunction "C_2") (pintype "passive"))
      (node (ref "R24") (pin "2") (pinfunction "2_2") (pintype "passive"))
    )
    (net (code "89") (name "/P3_R") (class "Default")
      (node (ref "IC1") (pin "90") (pinfunction "P1[10]/__ENET_RXD1_90") (pintype "bidirectional"))
      (node (ref "R12") (pin "2") (pinfunction "2_2") (pintype "passive"))
    )
    (net (code "90") (name "/P4") (class "Default")
      (node (ref "IC1") (pin "39") (pinfunction "P1[25]/MCOA1/__MAT1[1]_39") (pintype "bidirectional"))
      (node (ref "IC67") (pin "17") (pinfunction "PC2/SYNC/ASYNC/OC0C/OC0BLS/RXD0_17") (pintype "bidirectional"))
      (node (ref "R175") (pin "1") (pinfunction "1_1") (pintype "passive"))
    )
    (net (code "91") (name "/P4_RED") (class "Default")
      (node (ref "LED17") (pin "K") (pinfunction "K_K") (pintype "passive"))
      (node (ref "R175") (pin "2") (pinfunction "2_2") (pintype "passive"))
    )
    (net (code "92") (name "/PDI_DATA") (class "Default")
      (node (ref "CON1") (pin "1") (pinfunction "MISO_1") (pintype "passive"))
      (node (ref "IC67") (pin "89") (pinfunction "PDI/PDI_DATA_89") (pintype "bidirectional"))
    )
    (net (code "93") (name "/PGOOD_P1V0") (class "Default")
      (node (ref "IC1") (pin "26") (pinfunction "P3[26]/STCLK/__MAT0[1]/PWM1[3]_26") (pintype "bidirectional"))
      (node (ref "IC67") (pin "7") (pinfunction "PB2/SYNC/ASYNC/ADC2/AC2/DAC0_7") (pintype "bidirectional"))
    )
    (net (code "94") (name "/PROGRAM_B") (class "Default")
      (node (ref "R152") (pin "2") (pinfunction "2_2") (pintype "passive"))
      (node (ref "R34") (pin "2") (pinfunction "2_2") (pintype "passive"))
    )
    (net (code "95") (name "/PROGRAM_B_L") (class "Default")
      (node (ref "IC1") (pin "61") (pinfunction "P0[17]/CTS1/__MISO0/MISO_61") (pintype "bidirectional"))
      (node (ref "R152") (pin "1") (pinfunction "1_1") (pintype "passive"))
    )
    (net (code "96") (name "/PROGRAM_B_R") (class "Default")
      (node (ref "IC67") (pin "48") (pinfunction "PF3/SYNC/OC0D/TXD0_48") (pintype "bidirectional"))
      (node (ref "R34") (pin "1") (pinfunction "1_1") (pintype "passive"))
    )
    (net (code "97") (name "/PROG_RxD") (class "Default")
      (node (ref "IC1") (pin "99") (pinfunction "P0[3]/RXD0/AD0[6]_99") (pintype "bidirectional"))
      (node (ref "JP2") (pin "9") (pinfunction "9_9") (pintype "passive"))
    )
    (net (code "98") (name "/PROG_TxD") (class "Default")
      (node (ref "IC1") (pin "98") (pinfunction "P0[2]/TXD0/AD0[7]_98") (pintype "bidirectional"))
      (node (ref "JP2") (pin "3") (pinfunction "3_3") (pintype "passive"))
      (node (ref "R335") (pin "2") (pinfunction "2_2") (pintype "passive"))
    )
    (net (code "99") (name "/RESETn") (class "Default")
      (node (ref "IC1") (pin "36") (pinfunction "P1[22]/MCOB0/__USB_PWRD/__MAT1[0]_36") (pintype "bidirectional"))
      (node (ref "IC67") (pin "8") (pinfunction "PB3/SYNC/ADC3/AC3/DAC1_8") (pintype "bidirectional"))
    )
    (net (code "100") (name "/RST") (class "Default")
      (node (ref "CON1") (pin "5") (pinfunction "~{RESET}_5") (pintype "passive"))
      (node (ref "D1") (pin "A") (pinfunction "A_A") (pintype "passive"))
      (node (ref "IC1") (pin "17") (pinfunction "~{RESET}_17") (pintype "input"))
      (node (ref "IC67") (pin "90") (pinfunction "~{RESET}/PDI_CLOCK_90") (pintype "input"))
      (node (ref "JP1") (pin "6") (pinfunction "6_6") (pintype "passive"))
      (node (ref "JP2") (pin "6") (pinfunction "6_6") (pintype "passive"))
      (node (ref "R2") (pin "1") (pinfunction "1_1") (pintype "passive"))
    )
    (net (code "101") (name "/RST_K") (class "Default")
      (node (ref "D1") (pin "K") (pinfunction "K_K") (pintype "passive"))
      (node (ref "IC3") (pin "2") (pinfunction "~{RST}_2") (pintype "output"))
    )
    (net (code "102") (name "/RTM_PS#") (class "Default")
      (node (ref "IC1") (pin "29") (pinfunction "P0[29]/USB_D+_29") (pintype "bidirectional"))
      (node (ref "IC67") (pin "31") (pinfunction "PD6/SYNC/D-/RXD1/MISO_31") (pintype "bidirectional"))
    )
    (net (code "103") (name "/RXD") (class "Default")
      (node (ref "IC1") (pin "85") (pinfunction "P4[29]/TX_MCLK/__MAT2[1]/RXD3_85") (pintype "bidirectional"))
      (node (ref "IC67") (pin "27") (pinfunction "PD2/SYNC/ASYNC/OC0C/RXD0_27") (pintype "bidirectional"))
    )
    (net (code "104") (name "/SCANSTA_ADR0") (class "Default")
      (node (ref "IC1") (pin "75") (pinfunction "P2[0]/PWM1[1]/__TXD1_75") (pintype "bidirectional"))
      (node (ref "IC67") (pin "95") (pinfunction "PA0/SYNC/ADC0/AC0/AREF_95") (pintype "bidirectional"))
    )
    (net (code "105") (name "/SCANSTA_ADR1") (class "Default")
      (node (ref "IC1") (pin "74") (pinfunction "P2[1]/PWM1[2]/__RXD1_74") (pintype "bidirectional"))
      (node (ref "IC67") (pin "96") (pinfunction "PA1/SYNC/ADC1/AC1_96") (pintype "bidirectional"))
    )
    (net (code "106") (name "/SCANSTA_ADR2") (class "Default")
      (node (ref "IC1") (pin "73") (pinfunction "P2[2]/PWM1[3]/__CTS1/__TRACEDATA[3]_73") (pintype "bidirectional"))
      (node (ref "IC67") (pin "97") (pinfunction "PA2/SYNC/ASYNC/ADC2/AC2/DAC0_97") (pintype "bidirectional"))
    )
    (net (code "107") (name "/SCANSTA_ADR3") (class "Default")
      (node (ref "IC1") (pin "70") (pinfunction "P2[3]/PWM1[4]/__DCD1/__TRACEDATA[2]_70") (pintype "bidirectional"))
      (node (ref "IC67") (pin "98") (pinfunction "PA3/SYNC/ADC3/AC3/DAC1_98") (pintype "bidirectional"))
    )
    (net (code "108") (name "/SCANSTA_ADR4") (class "Default")
      (node (ref "IC1") (pin "69") (pinfunction "P2[4]/PWM1[5]/__DSR1/__TRACEDATA[1]_69") (pintype "bidirectional"))
      (node (ref "IC67") (pin "99") (pinfunction "PA4/SYNC/ADC4/AC4_99") (pintype "bidirectional"))
    )
    (net (code "109") (name "/SCANSTA_ADR5") (class "Default")
      (node (ref "IC1") (pin "68") (pinfunction "P2[5]/PWM1[6]/__DTR1/__TRACEDATA[0]_68") (pintype "bidirectional"))
      (node (ref "IC67") (pin "100") (pinfunction "PA5/SYNC/ADC5/AC5_100") (pintype "bidirectional"))
    )
    (net (code "110") (name "/SCANSTA_ADR6") (class "Default")
      (node (ref "IC1") (pin "67") (pinfunction "P2[6]/PCAP1[0]/__RI1/TRACECLK_67") (pintype "bidirectional"))
      (node (ref "IC67") (pin "1") (pinfunction "PA6/SYNC/ADC6/AC6_1") (pintype "bidirectional"))
    )
    (net (code "111") (name "/SCANSTA_RSTn") (class "Default")
      (node (ref "IC1") (pin "66") (pinfunction "P2[7]/RD2/__RTS1_66") (pintype "bidirectional"))
      (node (ref "IC67") (pin "2") (pinfunction "PA7/SYNC/ADC7/AC7/AC0OUT_2") (pintype "bidirectional"))
    )
    (net (code "112") (name "/SCL0") (class "Default")
      (node (ref "IC1") (pin "24") (pinfunction "P0[28]/SCL0/__USB_SCL_24") (pintype "bidirectional"))
      (node (ref "IC4") (pin "4") (pinfunction "4_4") (pintype "passive"))
      (node (ref "IC67") (pin "16") (pinfunction "PC1/SYNC/OC0B/OC0AHS/XCK0/SCL_16") (pintype "bidirectional"))
      (node (ref "R47") (pin "2") (pinfunction "2_2") (pintype "passive"))
    )
    (net (code "113") (name "/SCL1") (class "Default")
      (node (ref "IC1") (pin "58") (pinfunction "P0[20]/DTR1/SCL1_58") (pintype "bidirectional"))
      (node (ref "IC67") (pin "36") (pinfunction "PE1/SYNC/OC0B/OC0AHS/XCK0/SCL_36") (pintype "bidirectional"))
      (node (ref "R170") (pin "2") (pinfunction "2_2") (pintype "passive"))
    )
    (net (code "114") (name "/SCL2") (class "Default")
      (node (ref "IC1") (pin "49") (pinfunction "P0[11]/RXD2/__SCL2/MAT3[1]_49") (pintype "bidirectional"))
      (node (ref "IC67") (pin "46") (pinfunction "PF1/SYNC/OC0B/XCK0/SCL_46") (pintype "bidirectional"))
      (node (ref "R172") (pin "2") (pinfunction "2_2") (pintype "passive"))
    )
    (net (code "115") (name "/SDA0") (class "Default")
      (node (ref "IC1") (pin "25") (pinfunction "P0[27]/SDA0/__USB_SDA_25") (pintype "bidirectional"))
      (node (ref "IC4") (pin "6") (pinfunction "6_6") (pintype "passive"))
      (node (ref "IC67") (pin "15") (pinfunction "PC0/SYNC/OC0A/OC0ALS/SDA_15") (pintype "bidirectional"))
      (node (ref "R169") (pin "2") (pinfunction "2_2") (pintype "passive"))
    )
    (net (code "116") (name "/SDA1") (class "Default")
      (node (ref "IC1") (pin "59") (pinfunction "P0[19]/DSR1/__SDA1_59") (pintype "bidirectional"))
      (node (ref "IC67") (pin "35") (pinfunction "PE0/SYNC/OC0A/OC0ALS/SDA_35") (pintype "bidirectional"))
      (node (ref "R171") (pin "2") (pinfunction "2_2") (pintype "passive"))
    )
    (net (code "117") (name "/SDA2") (class "Default")
      (node (ref "IC1") (pin "48") (pinfunction "P0[10]/TXD2/__SDA2/MAT3[0]_48") (pintype "bidirectional"))
      (node (ref "IC67") (pin "45") (pinfunction "PF0/SYNC/OC0A/SDA_45") (pintype "bidirectional"))
      (node (ref "R173") (pin "2") (pinfunction "2_2") (pintype "passive"))
    )
    (net (code "118") (name "/SW") (class "Default")
      (node (ref "IC1") (pin "51") (pinfunction "P2[12]/~{EINT2}/__I2STX_WS_51") (pintype "bidirectional"))
      (node (ref "IC67") (pin "37") (pinfunction "PE2/SYNC/ASYNC/OC0C/OC0BLS/RXD0_37") (pintype "bidirectional"))
      (node (ref "R238") (pin "1") (pinfunction "1_1") (pintype "passive"))
    )
    (net (code "119") (name "/SWCLK") (class "Default")
      (node (ref "IC1") (pin "5") (pinfunction "TCK/SWDCLK_5") (pintype "input"))
      (node (ref "IC67") (pin "11") (pinfunction "PB6/SYNC/ADC6/AC6/TCK_11") (pintype "bidirectional"))
      (node (ref "JP1") (pin "1") (pinfunction "1_1") (pintype "passive"))
      (node (ref "JP2") (pin "1") (pinfunction "1_1") (pintype "passive"))
      (node (ref "R5") (pin "1") (pinfunction "1_1") (pintype "passive"))
    )
    (net (code "120") (name "/SWDIO") (class "Default")
      (node (ref "IC1") (pin "3") (pinfunction "TMS/SWDIO_3") (pintype "bidirectional"))
      (node (ref "IC67") (pin "9") (pinfunction "PB4/SYNC/ADC4/AC4/TMS_9") (pintype "bidirectional"))
      (node (ref "JP1") (pin "5") (pinfunction "5_5") (pintype "passive"))
      (node (ref "JP2") (pin "5") (pinfunction "5_5") (pintype "passive"))
      (node (ref "R4") (pin "1") (pinfunction "1_1") (pintype "passive"))
    )
    (net (code "121") (name "/TCLK_A_C_SEL") (class "Default")
      (node (ref "IC67") (pin "61") (pinfunction "PH6/SYNC/CKE/~{CS2}/A18_61") (pintype "bidirectional"))
      (node (ref "R335") (pin "1") (pinfunction "1_1") (pintype "passive"))
    )
    (net (code "122") (name "/TDI") (class "Default")
      (node (ref "IC1") (pin "2") (pinfunction "TDI_2") (pintype "input"))
      (node (ref "IC67") (pin "10") (pinfunction "PB5/SYNC/ADC5/AC5/TDI_10") (pintype "bidirectional"))
      (node (ref "JP1") (pin "9") (pinfunction "9_9") (pintype "passive"))
    )
    (net (code "123") (name "/TDO") (class "Default")
      (node (ref "IC1") (pin "1") (pinfunction "TDO/SWO_1") (pintype "output"))
      (node (ref "IC67") (pin "12") (pinfunction "PB7/SYNC/ADC7/AC7/AC0OUT/TDO_12") (pintype "bidirectional"))
      (node (ref "JP1") (pin "3") (pinfunction "3_3") (pintype "passive"))
    )
    (net (code "124") (name "/TP1") (class "Default")
      (node (ref "IC67") (pin "86") (pinfunction "PQ1/SYNC/TOSC2_86") (pintype "bidirectional"))
      (node (ref "TP1") (pin "1") (pintype "passive"))
    )
    (net (code "125") (name "/TP2") (class "Default")
      (node (ref "IC67") (pin "85") (pinfunction "PQ0/SYNC/TOSC1_85") (pintype "bidirectional"))
      (node (ref "TP2") (pin "1") (pintype "passive"))
    )
    (net (code "126") (name "/TP10") (class "Default")
      (node (ref "IC67") (pin "38") (pinfunction "PE3/SYNC/OC0D/OC0BHS/TXD0_38") (pintype "bidirectional"))
      (node (ref "TP10") (pin "1") (pintype "passive"))
    )
    (net (code "127") (name "/TRST") (class "Default")
      (node (ref "IC1") (pin "4") (pinfunction "~{TRST}_4") (pintype "input"))
      (node (ref "JP1") (pin "8") (pinfunction "8_8") (pintype "passive"))
      (node (ref "R3") (pin "1") (pinfunction "1_1") (pintype "passive"))
    )
    (net (code "128") (name "/TXD") (class "Default")
      (node (ref "IC1") (pin "82") (pinfunction "P4[28]/RX_MCLK/__MAT2[0]/TXD3_82") (pintype "bidirectional"))
      (node (ref "IC67") (pin "28") (pinfunction "PD3/SYNC/OC0D/TXD0_28") (pintype "bidirectional"))
    )
    (net (code "129") (name "/UPDATEn") (class "Default")
      (node (ref "IC1") (pin "40") (pinfunction "P1[26]/MCOB1/__PWM1[6]/CAP0[0]_40") (pintype "bidirectional"))
      (node (ref "IC67") (pin "22") (pinfunction "PC7/SYNC/OC0DHS/TXD1/SCK/CLKOUT/EVOUT_22") (pintype "bidirectional"))
    )
    (net (code "134") (name "/XTAL1") (class "Default")
      (node (ref "C435") (pin "2") (pinfunction "2_2") (pintype "passive"))
      (node (ref "IC67") (pin "92") (pinfunction "PR1/SYNC/XTAL1_92") (pintype "bidirectional"))
      (node (ref "X2") (pin "1") (pinfunction "1_1") (pintype "passive"))
    )
    (net (code "135") (name "/XTAL2") (class "Default")
      (node (ref "C444") (pin "2") (pinfunction "2_2") (pintype "passive"))
      (node (ref "IC67") (pin "91") (pinfunction "PR0/SYNC/XTAL2_91") (pintype "bidirectional"))
      (node (ref "X2") (pin "2") (pinfunction "2_2") (pintype "passive"))
    )
    (net (code "136") (name "/temp_SCL") (class "Default")
      (node (ref "IC1") (pin "47") (pinfunction "P0[1]/TD1/RXD3/__SCL1_47") (pintype "bidirectional"))
      (node (ref "IC67") (pin "26") (pinfunction "PD1/SYNC/OC0B/XCK0/SCL_26") (pintype "bidirectional"))
      (node (ref "R176") (pin "2") (pinfunction "2_2") (pintype "passive"))
    )
    (net (code "137") (name "/temp_SDA") (class "Default")
      (node (ref "IC1") (pin "46") (pinfunction "P0[0]/RD1/TXD3/__SDA1_46") (pintype "bidirectional"))
      (node (ref "IC67") (pin "25") (pinfunction "PD0/SYNC/OC0A/SDA_25") (pintype "bidirectional"))
      (node (ref "R174") (pin "2") (pinfunction "2_2") (pintype "passive"))
    )
    (net (code "144") (name "GND") (class "Default")
      (node (ref "C18") (pin "1") (pinfunction "1_1") (pintype "passive"))
      (node (ref "C19") (pin "1") (pinfunction "1_1") (pintype "passive"))
      (node (ref "C21") (pin "1") (pinfunction "1_1") (pintype "passive"))
      (node (ref "C22") (pin "1") (pinfunction "1_1") (pintype "passive"))
      (node (ref "C23") (pin "1") (pinfunction "1_1") (pintype "passive"))
      (node (ref "C24") (pin "1") (pinfunction "1_1") (pintype "passive"))
      (node (ref "C25") (pin "1") (pinfunction "1_1") (pintype "passive"))
      (node (ref "C26") (pin "1") (pinfunction "1_1") (pintype "passive"))
      (node (ref "C27") (pin "1") (pinfunction "1_1") (pintype "passive"))
      (node (ref "C28") (pin "2") (pinfunction "2_2") (pintype "passive"))
      (node (ref "C435") (pin "1") (pinfunction "1_1") (pintype "passive"))
      (node (ref "C436") (pin "1") (pinfunction "1_1") (pintype "passive"))
      (node (ref "C437") (pin "1") (pinfunction "1_1") (pintype "passive"))
      (node (ref "C438") (pin "1") (pinfunction "1_1") (pintype "passive"))
      (node (ref "C439") (pin "1") (pinfunction "1_1") (pintype "passive"))
      (node (ref "C440") (pin "1") (pinfunction "1_1") (pintype "passive"))
      (node (ref "C441") (pin "1") (pinfunction "1_1") (pintype "passive"))
      (node (ref "C442") (pin "1") (pinfunction "1_1") (pintype "passive"))
      (node (ref "C443") (pin "1") (pinfunction "1_1") (pintype "passive"))
      (node (ref "C444") (pin "1") (pinfunction "1_1") (pintype "passive"))
      (node (ref "C445") (pin "2") (pinfunction "2_2") (pintype "passive"))
      (node (ref "CON1") (pin "6") (pinfunction "GND_6") (pintype "passive"))
      (node (ref "IC1") (pin "11") (pinfunction "VSSA_11") (pintype "power_in"))
      (node (ref "IC1") (pin "15") (pinfunction "VREFN_15") (pintype "power_in"))
      (node (ref "IC1") (pin "31") (pinfunction "VSS_31") (pintype "power_in"))
      (node (ref "IC1") (pin "41") (pinfunction "VSS_41") (pintype "power_in"))
      (node (ref "IC1") (pin "55") (pinfunction "VSS_55") (pintype "power_in"))
      (node (ref "IC1") (pin "72") (pinfunction "VSS_72") (pintype "power_in"))
      (node (ref "IC1") (pin "83") (pinfunction "VSS_83") (pintype "power_in"))
      (node (ref "IC1") (pin "97") (pinfunction "VSS_97") (pintype "power_in"))
      (node (ref "IC3") (pin "1") (pinfunction "Vss_1") (pintype "power_in"))
      (node (ref "IC4") (pin "2") (pinfunction "2_2") (pintype "passive"))
      (node (ref "IC4") (pin "5") (pinfunction "5_5") (pintype "passive"))
      (node (ref "IC5") (pin "2") (pinfunction "2_2") (pintype "passive"))
      (node (ref "IC5") (pin "5") (pinfunction "5_5") (pintype "passive"))
      (node (ref "IC67") (pin "13") (pinfunction "GND_13") (pintype "power_in"))
      (node (ref "IC67") (pin "23") (pinfunction "GND_23") (pintype "power_in"))
      (node (ref "IC67") (pin "3") (pinfunction "GND_3") (pintype "power_in"))
      (node (ref "IC67") (pin "33") (pinfunction "GND_33") (pintype "power_in"))
      (node (ref "IC67") (pin "43") (pinfunction "GND_43") (pintype "power_in"))
      (node (ref "IC67") (pin "53") (pinfunction "GND_53") (pintype "power_in"))
      (node (ref "IC67") (pin "63") (pinfunction "GND_63") (pintype "power_in"))
      (node (ref "IC67") (pin "73") (pinfunction "GND_73") (pintype "power_in"))
      (node (ref "IC67") (pin "84") (pinfunction "GND_84") (pintype "power_in"))
      (node (ref "IC67") (pin "93") (pinfunction "GND_93") (pintype "power_in"))
      (node (ref "JP1") (pin "10") (pinfunction "10_10") (pintype "passive"))
      (node (ref "JP1") (pin "2") (pinfunction "2_2") (pintype "passive"))
      (node (ref "JP2") (pin "10") (pinfunction "10_10") (pintype "passive"))
      (node (ref "JP2") (pin "2") (pinfunction "2_2") (pintype "passive"))
      (node (ref "R5") (pin "2") (pinfunction "2_2") (pintype "passive"))
    )
    (net (code "145") (name "P3V3MP") (class "Default")
      (node (ref "C21") (pin "2") (pinfunction "2_2") (pintype "passive"))
      (node (ref "C22") (pin "2") (pinfunction "2_2") (pintype "passive"))
      (node (ref "C23") (pin "2") (pinfunction "2_2") (pintype "passive"))
      (node (ref "C24") (pin "2") (pinfunction "2_2") (pintype "passive"))
      (node (ref "C25") (pin "2") (pinfunction "2_2") (pintype "passive"))
      (node (ref "C26") (pin "2") (pinfunction "2_2") (pintype "passive"))
      (node (ref "C27") (pin "2") (pinfunction "2_2") (pintype "passive"))
      (node (ref "C436") (pin "2") (pinfunction "2_2") (pintype "passive"))
      (node (ref "C437") (pin "2") (pinfunction "2_2") (pintype "passive"))
      (node (ref "C438") (pin "2") (pinfunction "2_2") (pintype "passive"))
      (node (ref "C439") (pin "2") (pinfunction "2_2") (pintype "passive"))
      (node (ref "C440") (pin "2") (pinfunction "2_2") (pintype "passive"))
      (node (ref "C441") (pin "2") (pinfunction "2_2") (pintype "passive"))
      (node (ref "C442") (pin "2") (pinfunction "2_2") (pintype "passive"))
      (node (ref "C443") (pin "2") (pinfunction "2_2") (pintype "passive"))
      (node (ref "CON1") (pin "2") (pinfunction "VCC_2") (pintype "passive"))
      (node (ref "IC1") (pin "19") (pinfunction "VBAT_19") (pintype "power_in"))
      (node (ref "IC1") (pin "28") (pinfunction "VDD(3V3)_28") (pintype "power_in"))
      (node (ref "IC1") (pin "42") (pinfunction "VDD(REG)(3V3)_42") (pintype "power_in"))
      (node (ref "IC1") (pin "54") (pinfunction "VDD(3V3)_54") (pintype "power_in"))
      (node (ref "IC1") (pin "71") (pinfunction "VDD(3V3)_71") (pintype "power_in"))
      (node (ref "IC1") (pin "84") (pinfunction "VDD(REG)(3V3)_84") (pintype "power_in"))
      (node (ref "IC1") (pin "96") (pinfunction "VDD(3V3)_96") (pintype "power_in"))
      (node (ref "IC3") (pin "3") (pinfunction "Vcc_3") (pintype "power_in"))
      (node (ref "IC67") (pin "14") (pinfunction "VCC_14") (pintype "power_in"))
      (node (ref "IC67") (pin "24") (pinfunction "VCC_24") (pintype "power_in"))
      (node (ref "IC67") (pin "34") (pinfunction "VCC_34") (pintype "power_in"))
      (node (ref "IC67") (pin "44") (pinfunction "VCC_44") (pintype "power_in"))
      (node (ref "IC67") (pin "54") (pinfunction "VCC_54") (pintype "power_in"))
      (node (ref "IC67") (pin "64") (pinfunction "VCC_64") (pintype "power_in"))
      (node (ref "IC67") (pin "74") (pinfunction "VCC_74") (pintype "power_in"))
      (node (ref "IC67") (pin "83") (pinfunction "VCC_83") (pintype "power_in"))
      (node (ref "JP1") (pin "4") (pinfunction "4_4") (pintype "passive"))
      (node (ref "JP2") (pin "4") (pinfunction "4_4") (pintype "passive"))
      (node (ref "L14") (pin "2") (pinfunction "2_2") (pintype "passive"))
      (node (ref "L4") (pin "1") (pinfunction "1_1") (pintype "passive"))
      (node (ref "LDx") (pin "1") (pinfunction "A_1") (pintype "passive"))
      (node (ref "LDy") (pin "1") (pinfunction "A_1") (pintype "passive"))
      (node (ref "LED17") (pin "A") (pinfunction "A_A") (pintype "passive"))
      (node (ref "R100") (pin "2") (pinfunction "2_2") (pintype "passive"))
      (node (ref "R101") (pin "2") (pinfunction "2_2") (pintype "passive"))
      (node (ref "R102") (pin "2") (pinfunction "2_2") (pintype "passive"))
      (node (ref "R123") (pin "2") (pinfunction "2_2") (pintype "passive"))
      (node (ref "R169") (pin "1") (pinfunction "1_1") (pintype "passive"))
      (node (ref "R170") (pin "1") (pinfunction "1_1") (pintype "passive"))
      (node (ref "R171") (pin "1") (pinfunction "1_1") (pintype "passive"))
      (node (ref "R172") (pin "1") (pinfunction "1_1") (pintype "passive"))
      (node (ref "R173") (pin "1") (pinfunction "1_1") (pintype "passive"))
      (node (ref "R174") (pin "1") (pinfunction "1_1") (pintype "passive"))
      (node (ref "R176") (pin "1") (pinfunction "1_1") (pintype "passive"))
      (node (ref "R19") (pin "2") (pinfunction "2_2") (pintype "passive"))
      (node (ref "R2") (pin "2") (pinfunction "2_2") (pintype "passive"))
      (node (ref "R238") (pin "2") (pinfunction "2_2") (pintype "passive"))
      (node (ref "R3") (pin "2") (pinfunction "2_2") (pintype "passive"))
      (node (ref "R4") (pin "2") (pinfunction "2_2") (pintype "passive"))
      (node (ref "R47") (pin "1") (pinfunction "1_1") (pintype "passive"))
      (node (ref "R6") (pin "2") (pinfunction "2_2") (pintype "passive"))
      (node (ref "R97") (pin "2") (pinfunction "2_2") (pintype "passive"))
      (node (ref "R98") (pin "2") (pinfunction "2_2") (pintype "passive"))
      (node (ref "R99") (pin "2") (pinfunction "2_2") (pintype "passive"))
    )
    (net (code "146") (name "unconnected-(CON1-MOSI-Pad4)") (class "Default")
      (node (ref "CON1") (pin "4") (pinfunction "MOSI_4") (pintype "passive"))
    )
    (net (code "147") (name "unconnected-(CON1-SCK-Pad3)") (class "Default")
      (node (ref "CON1") (pin "3") (pinfunction "SCK_3") (pintype "passive"))
    )
    (net (code "148") (name "unconnected-(IC1A-N.C.-Pad13)") (class "Default")
      (node (ref "IC1") (pin "13") (pinfunction "N.C._13") (pintype "tri_state"))
    )
    (net (code "149") (name "unconnected-(IC1A-RTCK-Pad100)") (class "Default")
      (node (ref "IC1") (pin "100") (pinfunction "RTCK_100") (pintype "output"))
    )
    (net (code "150") (name "unconnected-(IC1A-RTCX1-Pad16)") (class "Default")
      (node (ref "IC1") (pin "16") (pinfunction "RTCX1_16") (pintype "input+no_connect"))
    )
    (net (code "151") (name "unconnected-(IC1A-RTCX2-Pad18)") (class "Default")
      (node (ref "IC1") (pin "18") (pinfunction "RTCX2_18") (pintype "output+no_connect"))
    )
    (net (code "152") (name "unconnected-(IC1A-~{RSTOUT}-Pad14)") (class "Default")
      (node (ref "IC1") (pin "14") (pinfunction "~{RSTOUT}_14") (pintype "output"))
    )
    (net (code "153") (name "unconnected-(IC4-Pad1)") (class "Default")
      (node (ref "IC4") (pin "1") (pinfunction "1_1") (pintype "passive"))
    )
    (net (code "154") (name "unconnected-(IC4-Pad3)") (class "Default")
      (node (ref "IC4") (pin "3") (pinfunction "3_3") (pintype "passive"))
    )
    (net (code "155") (name "unconnected-(IC5-Pad6)") (class "Default")
      (node (ref "IC5") (pin "6") (pinfunction "6_6") (pintype "passive"))
    )
    (net (code "156") (name "unconnected-(IC67A-PD4{slash}SYNC{slash}OC1A{slash}~{SS}-Pad29)") (class "Default")
      (node (ref "IC67") (pin "29") (pinfunction "PD4/SYNC/OC1A/~{SS}_29") (pintype "bidirectional"))
    )
    (net (code "157") (name "unconnected-(JP1-Pad7)") (class "Default")
      (node (ref "JP1") (pin "7") (pinfunction "7_7") (pintype "passive"))
    )
    (net (code "158") (name "unconnected-(JP2-Pad7)") (class "Default")
      (node (ref "JP2") (pin "7") (pinfunction "7_7") (pintype "passive"))
    )
  )
)
